# edges_v20.net
KiCad netlist of a schematic drawn in EAGLE
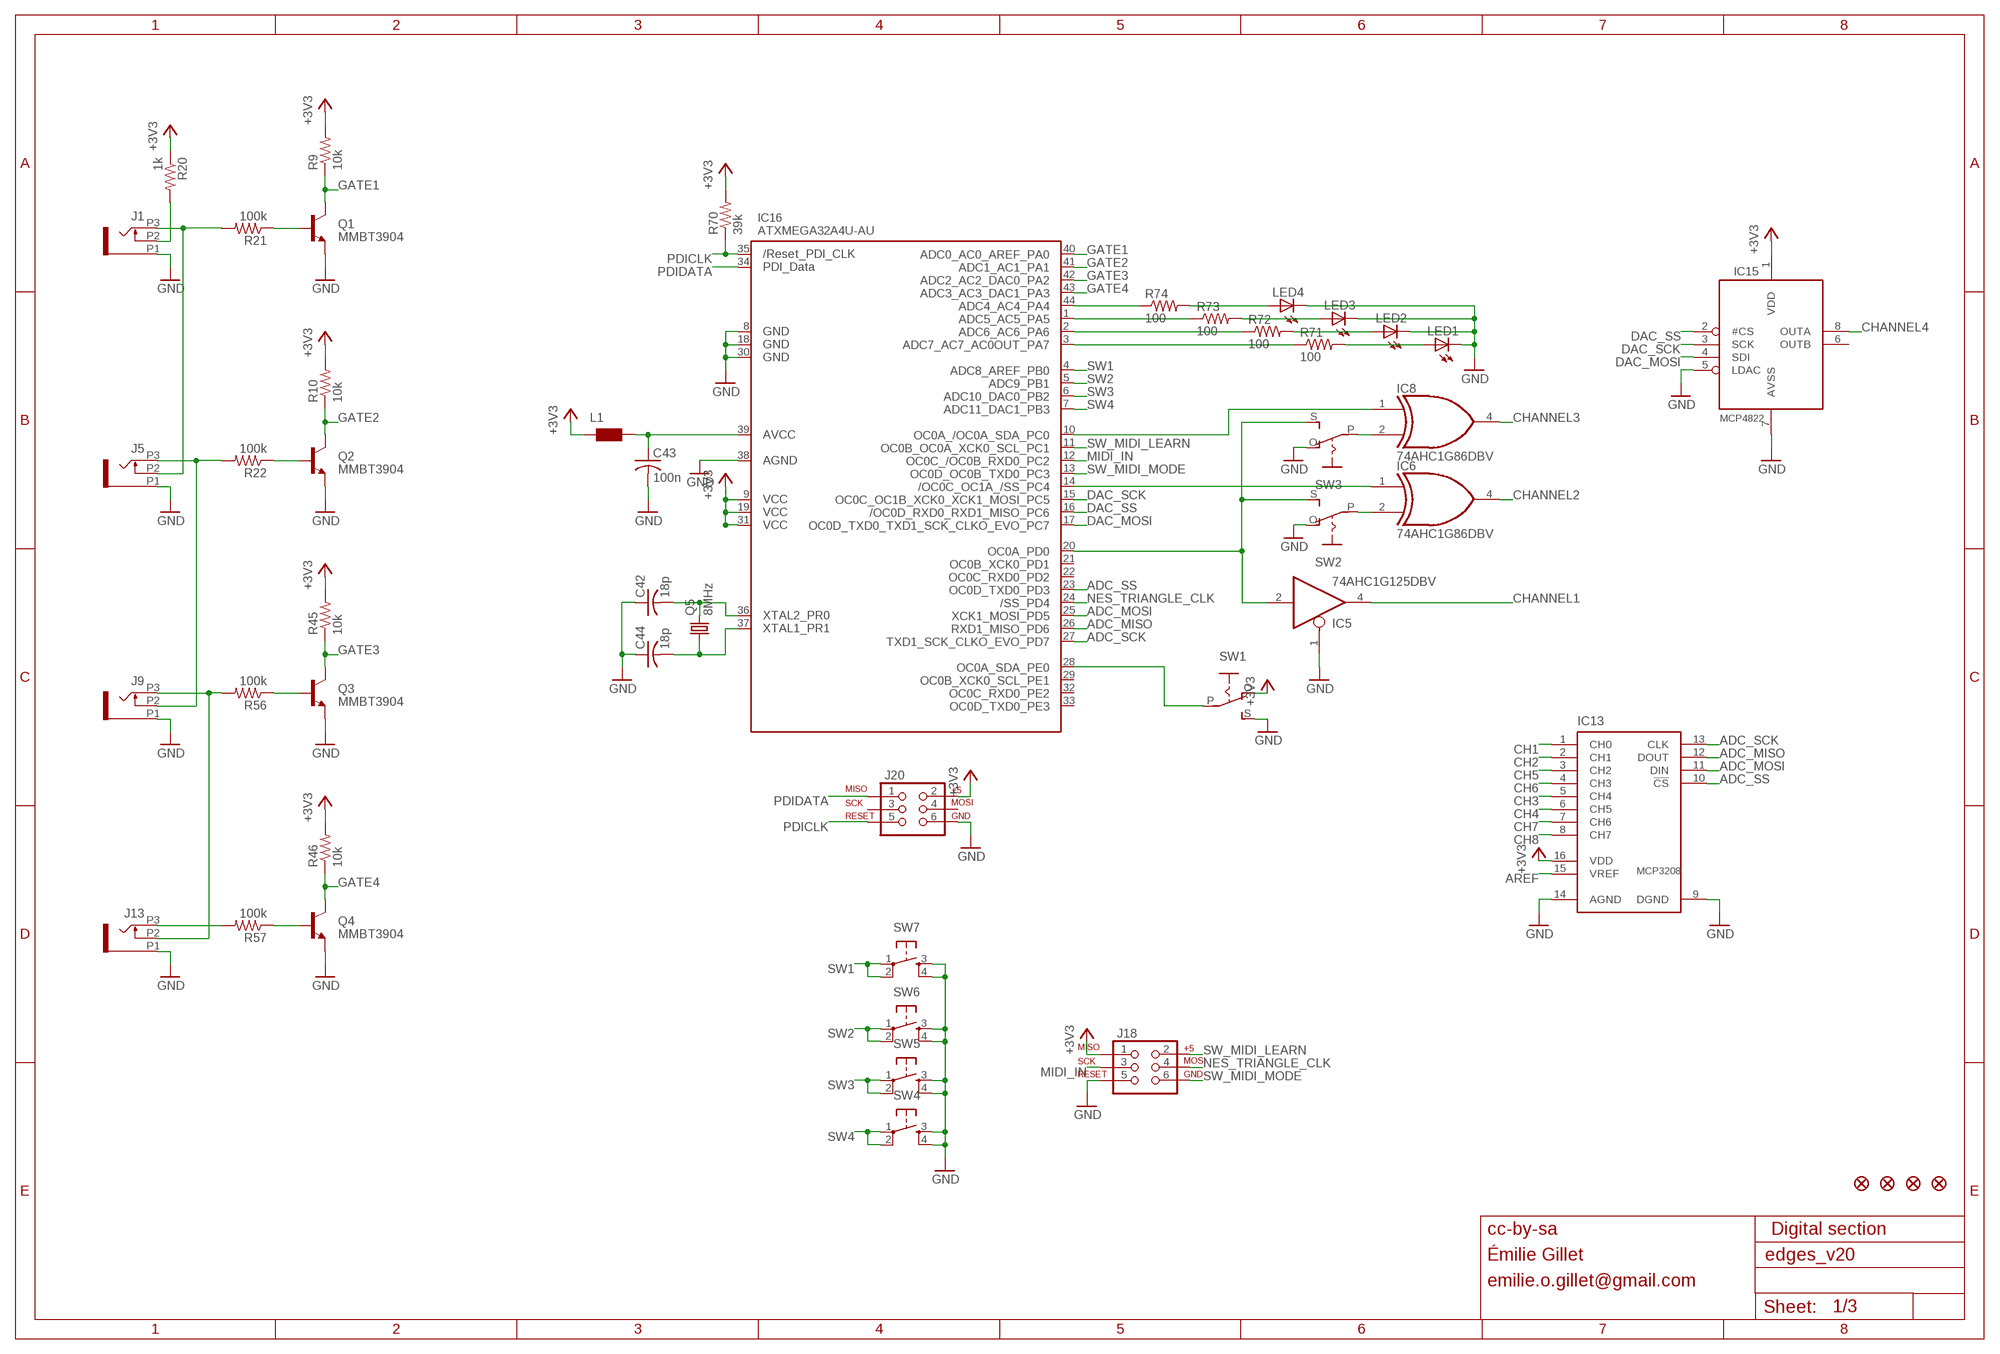
[diagram p0: schematic, sheet 1]
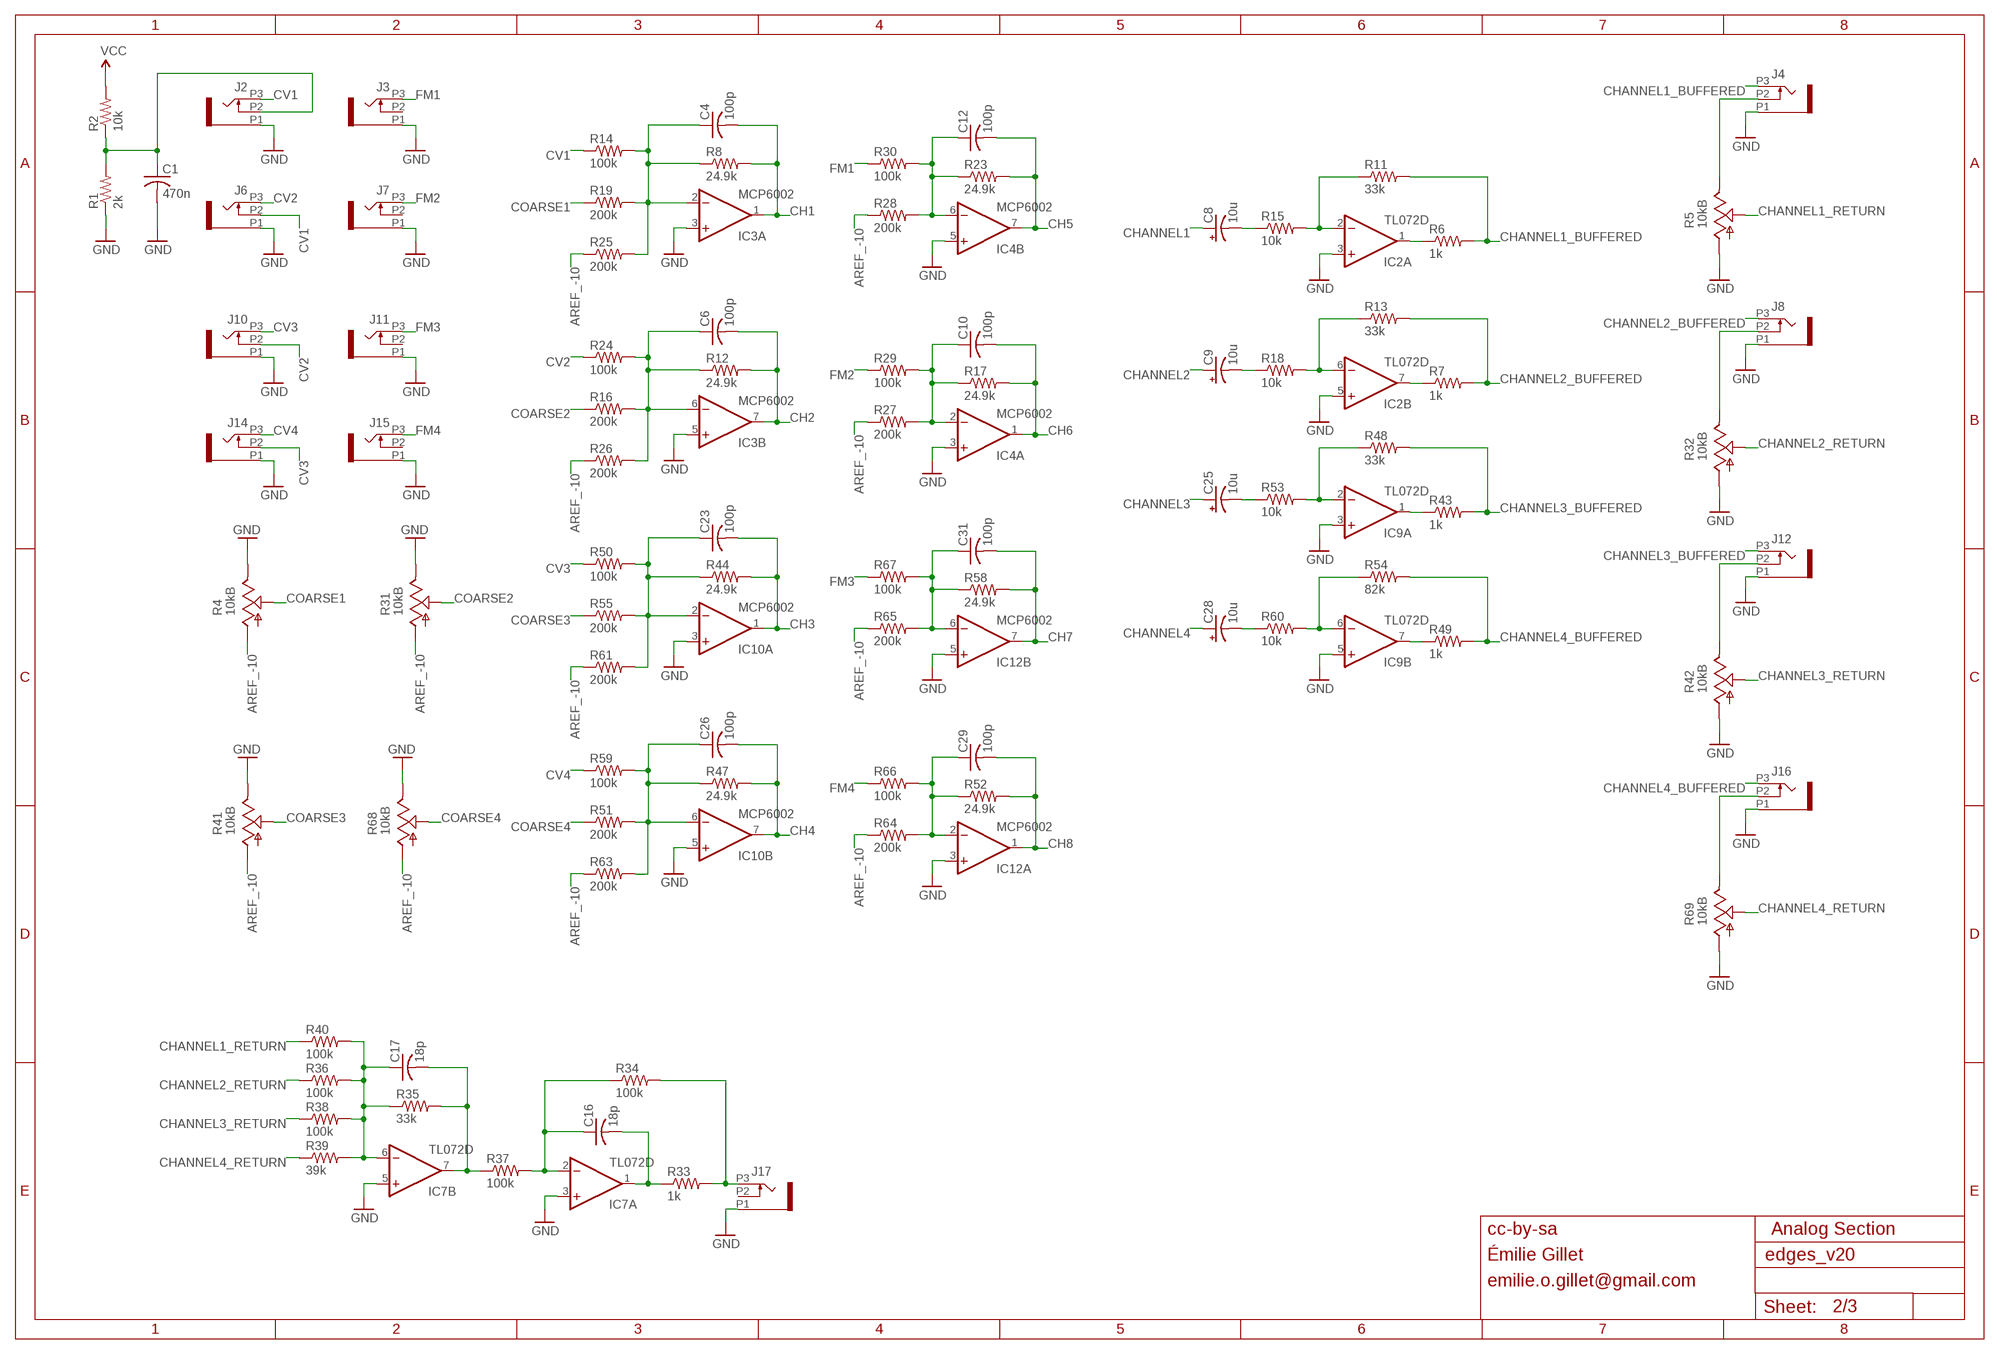
[diagram p1: schematic, sheet 2]
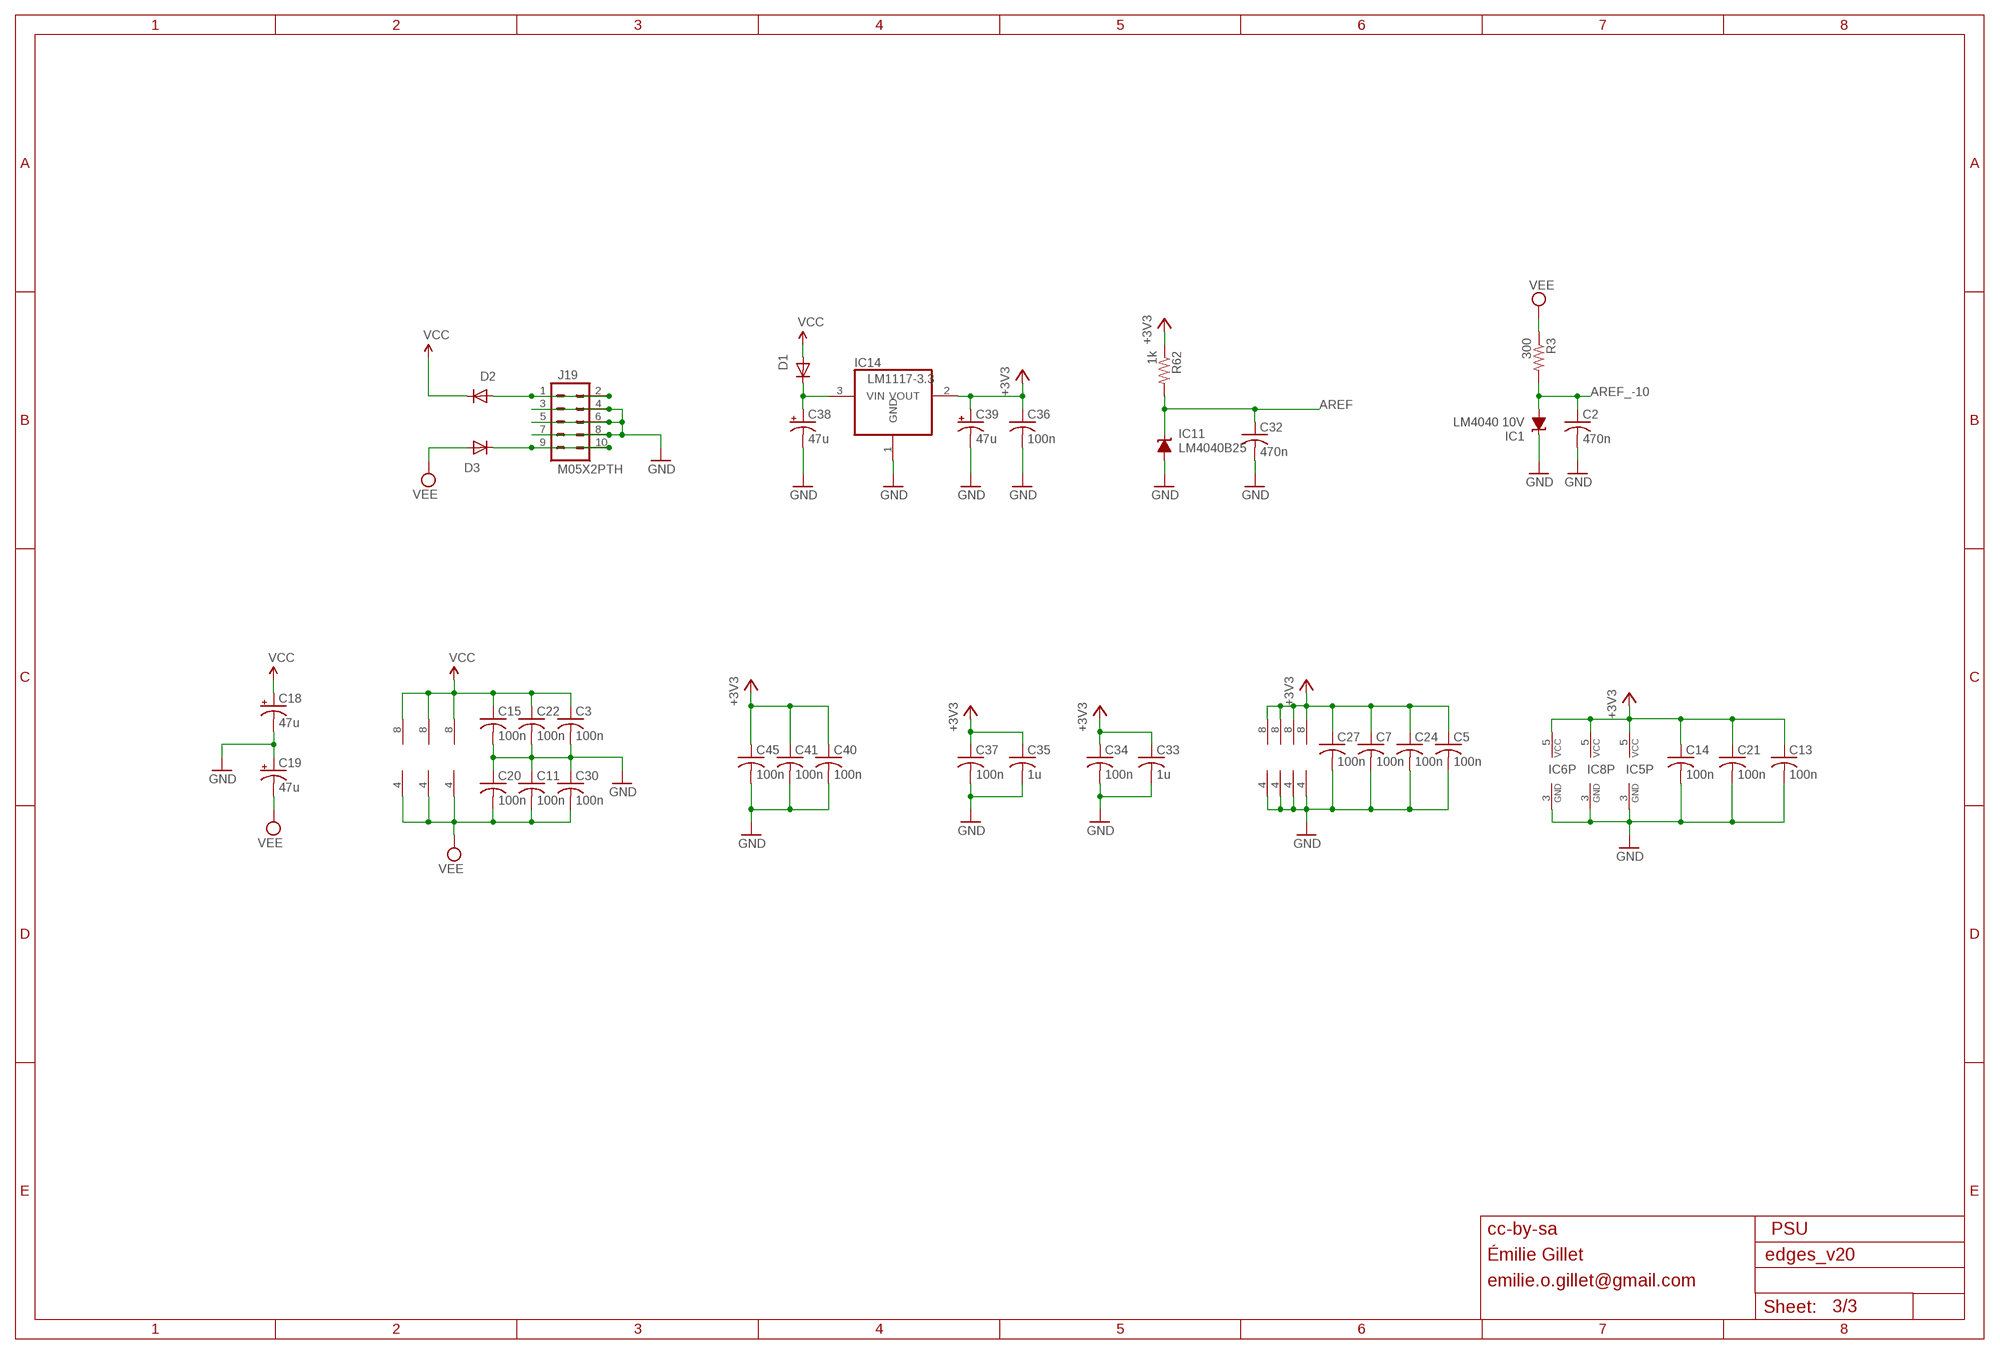
[diagram p2: schematic, sheet 3]

(export (version "E")
  (design (tool "Eeschema 10.0.6"))
  (components
    (comp (ref "C42")
      (value "18p")
      (footprint "eagle-import:C0603")
      (libsource (lib "eagle-import") (part "C-USC0603"))
    )
    (comp (ref "C43")
      (value "100n")
      (footprint "eagle-import:C0603")
      (libsource (lib "eagle-import") (part "C-USC0603"))
    )
    (comp (ref "C44")
      (value "18p")
      (footprint "eagle-import:C0603")
      (libsource (lib "eagle-import") (part "C-USC0603"))
    )
    (comp (ref "IC5")
      (value "74AHC1G125DBV")
      (footprint "eagle-import:SOT23-5")
      (libsource (lib "eagle-import") (part "741G125DBVAHC"))
    )
    (comp (ref "IC6")
      (value "74AHC1G86DBV")
      (footprint "eagle-import:SOT23-5")
      (libsource (lib "eagle-import") (part "741G86DBVAHC"))
    )
    (comp (ref "IC8")
      (value "74AHC1G86DBV")
      (footprint "eagle-import:SOT23-5")
      (libsource (lib "eagle-import") (part "741G86DBVAHC"))
    )
    (comp (ref "IC13")
      (value "MCP3208")
      (footprint "eagle-import:SO16")
      (libsource (lib "eagle-import") (part "MCP3208"))
    )
    (comp (ref "IC15")
      (value "MCP4822")
      (footprint "eagle-import:SO08")
      (libsource (lib "eagle-import") (part "MCP4822SO08"))
    )
    (comp (ref "IC16")
      (value "ATXMEGA32A4U-AU")
      (footprint "eagle-import:TQFP44")
      (libsource (lib "eagle-import") (part "AVR_XMEGA_A4_44A"))
    )
    (comp (ref "J1")
      (value "PJ301_THONKICONN6")
      (footprint "eagle-import:WQP_PJ_301M6")
      (libsource (lib "eagle-import") (part "PJ301_THONKICONN6"))
    )
    (comp (ref "J5")
      (value "PJ301_THONKICONN6")
      (footprint "eagle-import:WQP_PJ_301M6")
      (libsource (lib "eagle-import") (part "PJ301_THONKICONN6"))
    )
    (comp (ref "J9")
      (value "PJ301_THONKICONN6")
      (footprint "eagle-import:WQP_PJ_301M6")
      (libsource (lib "eagle-import") (part "PJ301_THONKICONN6"))
    )
    (comp (ref "J13")
      (value "PJ301_THONKICONN6")
      (footprint "eagle-import:WQP_PJ_301M6")
      (libsource (lib "eagle-import") (part "PJ301_THONKICONN6"))
    )
    (comp (ref "J18")
      (value "AVR_SPI_PRG_6PTH")
      (footprint "eagle-import:2X3")
      (libsource (lib "eagle-import") (part "AVR_SPI_PRG_6PTH"))
    )
    (comp (ref "J20")
      (value "AVR_SPI_PRG_6PTH")
      (footprint "eagle-import:2X3")
      (libsource (lib "eagle-import") (part "AVR_SPI_PRG_6PTH"))
    )
    (comp (ref "JP1")
      (value "FIDUCIAL1X2")
      (footprint "eagle-import:FIDUCIAL-1X2")
      (libsource (lib "eagle-import") (part "FIDUCIAL1X2"))
    )
    (comp (ref "JP2")
      (value "FIDUCIAL1X2")
      (footprint "eagle-import:FIDUCIAL-1X2")
      (libsource (lib "eagle-import") (part "FIDUCIAL1X2"))
    )
    (comp (ref "JP3")
      (value "FIDUCIAL1X2")
      (footprint "eagle-import:FIDUCIAL-1X2")
      (libsource (lib "eagle-import") (part "FIDUCIAL1X2"))
    )
    (comp (ref "JP4")
      (value "FIDUCIAL1X2")
      (footprint "eagle-import:FIDUCIAL-1X2")
      (libsource (lib "eagle-import") (part "FIDUCIAL1X2"))
    )
    (comp (ref "L1")
      (value "WE-CBF_0603")
      (footprint "eagle-import:0603")
      (libsource (lib "eagle-import") (part "WE-CBF_0603"))
    )
    (comp (ref "LED1")
      (value "LED3MM")
      (footprint "eagle-import:LED3MM")
      (libsource (lib "eagle-import") (part "LED3MM"))
    )
    (comp (ref "LED2")
      (value "LED3MM")
      (footprint "eagle-import:LED3MM")
      (libsource (lib "eagle-import") (part "LED3MM"))
    )
    (comp (ref "LED3")
      (value "LED3MM")
      (footprint "eagle-import:LED3MM")
      (libsource (lib "eagle-import") (part "LED3MM"))
    )
    (comp (ref "LED4")
      (value "LED3MM")
      (footprint "eagle-import:LED3MM")
      (libsource (lib "eagle-import") (part "LED3MM"))
    )
    (comp (ref "Q1")
      (value "MMBT3904")
      (footprint "eagle-import:SOT23-BEC")
      (libsource (lib "eagle-import") (part "-NPN-SOT23-BECMMBT3904LT1"))
    )
    (comp (ref "Q2")
      (value "MMBT3904")
      (footprint "eagle-import:SOT23-BEC")
      (libsource (lib "eagle-import") (part "-NPN-SOT23-BECMMBT3904LT1"))
    )
    (comp (ref "Q3")
      (value "MMBT3904")
      (footprint "eagle-import:SOT23-BEC")
      (libsource (lib "eagle-import") (part "-NPN-SOT23-BECMMBT3904LT1"))
    )
    (comp (ref "Q4")
      (value "MMBT3904")
      (footprint "eagle-import:SOT23-BEC")
      (libsource (lib "eagle-import") (part "-NPN-SOT23-BECMMBT3904LT1"))
    )
    (comp (ref "Q5")
      (value "8MHz")
      (footprint "eagle-import:HC49U70")
      (libsource (lib "eagle-import") (part "CRYSTALHC49U70"))
    )
    (comp (ref "R9")
      (value "10k")
      (footprint "eagle-import:R0603")
      (libsource (lib "eagle-import") (part "R-US_R0603"))
    )
    (comp (ref "R10")
      (value "10k")
      (footprint "eagle-import:R0603")
      (libsource (lib "eagle-import") (part "R-US_R0603"))
    )
    (comp (ref "R20")
      (value "1k")
      (footprint "eagle-import:R0603")
      (libsource (lib "eagle-import") (part "R-US_R0603"))
    )
    (comp (ref "R21")
      (value "100k")
      (footprint "eagle-import:R0603")
      (libsource (lib "eagle-import") (part "R-US_R0603"))
    )
    (comp (ref "R22")
      (value "100k")
      (footprint "eagle-import:R0603")
      (libsource (lib "eagle-import") (part "R-US_R0603"))
    )
    (comp (ref "R45")
      (value "10k")
      (footprint "eagle-import:R0603")
      (libsource (lib "eagle-import") (part "R-US_R0603"))
    )
    (comp (ref "R46")
      (value "10k")
      (footprint "eagle-import:R0603")
      (libsource (lib "eagle-import") (part "R-US_R0603"))
    )
    (comp (ref "R56")
      (value "100k")
      (footprint "eagle-import:R0603")
      (libsource (lib "eagle-import") (part "R-US_R0603"))
    )
    (comp (ref "R57")
      (value "100k")
      (footprint "eagle-import:R0603")
      (libsource (lib "eagle-import") (part "R-US_R0603"))
    )
    (comp (ref "R70")
      (value "39k")
      (footprint "eagle-import:R0603")
      (libsource (lib "eagle-import") (part "R-US_R0603"))
    )
    (comp (ref "R71")
      (value "100")
      (footprint "eagle-import:R0603")
      (libsource (lib "eagle-import") (part "R-US_R0603"))
    )
    (comp (ref "R72")
      (value "100")
      (footprint "eagle-import:R0603")
      (libsource (lib "eagle-import") (part "R-US_R0603"))
    )
    (comp (ref "R73")
      (value "100")
      (footprint "eagle-import:R0603")
      (libsource (lib "eagle-import") (part "R-US_R0603"))
    )
    (comp (ref "R74")
      (value "100")
      (footprint "eagle-import:R0603")
      (libsource (lib "eagle-import") (part "R-US_R0603"))
    )
    (comp (ref "SW1")
      (value "S-ON-ONSMALL_SLIDE")
      (footprint "eagle-import:ES_100SP1T6B11M2QEH_SMALL")
      (libsource (lib "eagle-import") (part "S-ON-ONSMALL_SLIDE"))
    )
    (comp (ref "SW2")
      (value "S-ON-ONSMALL_SLIDE")
      (footprint "eagle-import:ES_100SP1T6B11M2QEH_SMALL")
      (libsource (lib "eagle-import") (part "S-ON-ONSMALL_SLIDE"))
    )
    (comp (ref "SW3")
      (value "S-ON-ONSMALL_SLIDE")
      (footprint "eagle-import:ES_100SP1T6B11M2QEH_SMALL")
      (libsource (lib "eagle-import") (part "S-ON-ONSMALL_SLIDE"))
    )
    (comp (ref "SW4")
      (value "TAC_SWITCHPTH")
      (footprint "eagle-import:TACTILE-PTH")
      (libsource (lib "eagle-import") (part "TAC_SWITCHPTH"))
    )
    (comp (ref "SW5")
      (value "TAC_SWITCHPTH")
      (footprint "eagle-import:TACTILE-PTH")
      (libsource (lib "eagle-import") (part "TAC_SWITCHPTH"))
    )
    (comp (ref "SW6")
      (value "TAC_SWITCHPTH")
      (footprint "eagle-import:TACTILE-PTH")
      (libsource (lib "eagle-import") (part "TAC_SWITCHPTH"))
    )
    (comp (ref "SW7")
      (value "TAC_SWITCHPTH")
      (footprint "eagle-import:TACTILE-PTH")
      (libsource (lib "eagle-import") (part "TAC_SWITCHPTH"))
    )
    (comp (ref "C2")
      (value "470n")
      (footprint "eagle-import:C0603")
      (libsource (lib "eagle-import") (part "C-USC0603"))
    )
    (comp (ref "C3")
      (value "100n")
      (footprint "eagle-import:C0603")
      (libsource (lib "eagle-import") (part "C-USC0603"))
    )
    (comp (ref "C5")
      (value "100n")
      (footprint "eagle-import:C0603")
      (libsource (lib "eagle-import") (part "C-USC0603"))
    )
    (comp (ref "C7")
      (value "100n")
      (footprint "eagle-import:C0603")
      (libsource (lib "eagle-import") (part "C-USC0603"))
    )
    (comp (ref "C11")
      (value "100n")
      (footprint "eagle-import:C0603")
      (libsource (lib "eagle-import") (part "C-USC0603"))
    )
    (comp (ref "C13")
      (value "100n")
      (footprint "eagle-import:C0603")
      (libsource (lib "eagle-import") (part "C-USC0603"))
    )
    (comp (ref "C14")
      (value "100n")
      (footprint "eagle-import:C0603")
      (libsource (lib "eagle-import") (part "C-USC0603"))
    )
    (comp (ref "C15")
      (value "100n")
      (footprint "eagle-import:C0603")
      (libsource (lib "eagle-import") (part "C-USC0603"))
    )
    (comp (ref "C18")
      (value "47u")
      (footprint "eagle-import:PANASONIC_D")
      (libsource (lib "eagle-import") (part "CPOL-USD"))
    )
    (comp (ref "C19")
      (value "47u")
      (footprint "eagle-import:PANASONIC_D")
      (libsource (lib "eagle-import") (part "CPOL-USD"))
    )
    (comp (ref "C20")
      (value "100n")
      (footprint "eagle-import:C0603")
      (libsource (lib "eagle-import") (part "C-USC0603"))
    )
    (comp (ref "C21")
      (value "100n")
      (footprint "eagle-import:C0603")
      (libsource (lib "eagle-import") (part "C-USC0603"))
    )
    (comp (ref "C22")
      (value "100n")
      (footprint "eagle-import:C0603")
      (libsource (lib "eagle-import") (part "C-USC0603"))
    )
    (comp (ref "C24")
      (value "100n")
      (footprint "eagle-import:C0603")
      (libsource (lib "eagle-import") (part "C-USC0603"))
    )
    (comp (ref "C27")
      (value "100n")
      (footprint "eagle-import:C0603")
      (libsource (lib "eagle-import") (part "C-USC0603"))
    )
    (comp (ref "C30")
      (value "100n")
      (footprint "eagle-import:C0603")
      (libsource (lib "eagle-import") (part "C-USC0603"))
    )
    (comp (ref "C32")
      (value "470n")
      (footprint "eagle-import:C0603")
      (libsource (lib "eagle-import") (part "C-USC0603"))
    )
    (comp (ref "C33")
      (value "1u")
      (footprint "eagle-import:C0603")
      (libsource (lib "eagle-import") (part "C-USC0603"))
    )
    (comp (ref "C34")
      (value "100n")
      (footprint "eagle-import:C0603")
      (libsource (lib "eagle-import") (part "C-USC0603"))
    )
    (comp (ref "C35")
      (value "1u")
      (footprint "eagle-import:C0603")
      (libsource (lib "eagle-import") (part "C-USC0603"))
    )
    (comp (ref "C36")
      (value "100n")
      (footprint "eagle-import:C0603")
      (libsource (lib "eagle-import") (part "C-USC0603"))
    )
    (comp (ref "C37")
      (value "100n")
      (footprint "eagle-import:C0603")
      (libsource (lib "eagle-import") (part "C-USC0603"))
    )
    (comp (ref "C38")
      (value "47u")
      (footprint "eagle-import:PANASONIC_D")
      (libsource (lib "eagle-import") (part "CPOL-USD"))
    )
    (comp (ref "C39")
      (value "47u")
      (footprint "eagle-import:PANASONIC_D")
      (libsource (lib "eagle-import") (part "CPOL-USD"))
    )
    (comp (ref "C40")
      (value "100n")
      (footprint "eagle-import:C0603")
      (libsource (lib "eagle-import") (part "C-USC0603"))
    )
    (comp (ref "C41")
      (value "100n")
      (footprint "eagle-import:C0603")
      (libsource (lib "eagle-import") (part "C-USC0603"))
    )
    (comp (ref "C45")
      (value "100n")
      (footprint "eagle-import:C0603")
      (libsource (lib "eagle-import") (part "C-USC0603"))
    )
    (comp (ref "D1")
      (value "1N5819HW")
      (footprint "eagle-import:SOD123")
      (libsource (lib "eagle-import") (part "DIODE-SOD123"))
    )
    (comp (ref "D2")
      (value "1N5819HW")
      (footprint "eagle-import:SOD123")
      (libsource (lib "eagle-import") (part "DIODE-SOD123"))
    )
    (comp (ref "D3")
      (value "1N5819HW")
      (footprint "eagle-import:SOD123")
      (libsource (lib "eagle-import") (part "DIODE-SOD123"))
    )
    (comp (ref "IC1")
      (value "LM4040 10V")
      (footprint "eagle-import:DBZ_R-PDSO-G3")
      (libsource (lib "eagle-import") (part "LM4041DBZC12"))
    )
    (comp (ref "IC2")
      (value "TL072D")
      (footprint "eagle-import:SO08")
      (libsource (lib "eagle-import") (part "TL072D"))
    )
    (comp (ref "IC3")
      (value "MCP6002")
      (footprint "eagle-import:SO08")
      (libsource (lib "eagle-import") (part "TL072D"))
    )
    (comp (ref "IC4")
      (value "MCP6002")
      (footprint "eagle-import:SO08")
      (libsource (lib "eagle-import") (part "TL072D"))
    )
    (comp (ref "IC7")
      (value "TL072D")
      (footprint "eagle-import:SO08")
      (libsource (lib "eagle-import") (part "TL072D"))
    )
    (comp (ref "IC9")
      (value "TL072D")
      (footprint "eagle-import:SO08")
      (libsource (lib "eagle-import") (part "TL072D"))
    )
    (comp (ref "IC10")
      (value "MCP6002")
      (footprint "eagle-import:SO08")
      (libsource (lib "eagle-import") (part "TL072D"))
    )
    (comp (ref "IC11")
      (value "LM4040B25")
      (footprint "eagle-import:DBZ_R-PDSO-G3")
      (libsource (lib "eagle-import") (part "LM4041DBZB12"))
    )
    (comp (ref "IC12")
      (value "MCP6002")
      (footprint "eagle-import:SO08")
      (libsource (lib "eagle-import") (part "TL072D"))
    )
    (comp (ref "IC14")
      (value "LM1117-3.3")
      (footprint "eagle-import:SOT223")
      (libsource (lib "eagle-import") (part "REG1117"))
    )
    (comp (ref "J19")
      (value "M05X2PTH")
      (footprint "eagle-import:AVR_ICSP")
      (libsource (lib "eagle-import") (part "M05X2PTH"))
    )
    (comp (ref "R3")
      (value "300")
      (footprint "eagle-import:R0603")
      (libsource (lib "eagle-import") (part "resistor_R-US_R0603"))
    )
    (comp (ref "R62")
      (value "1k")
      (footprint "eagle-import:R0603")
      (libsource (lib "eagle-import") (part "R-US_R0603"))
    )
    (comp (ref "C1")
      (value "470n")
      (footprint "eagle-import:C0603")
      (libsource (lib "eagle-import") (part "C-USC0603"))
    )
    (comp (ref "C4")
      (value "100p")
      (footprint "eagle-import:C0603")
      (libsource (lib "eagle-import") (part "C-USC0603"))
    )
    (comp (ref "C6")
      (value "100p")
      (footprint "eagle-import:C0603")
      (libsource (lib "eagle-import") (part "C-USC0603"))
    )
    (comp (ref "C8")
      (value "10u")
      (footprint "eagle-import:PANASONIC_B")
      (libsource (lib "eagle-import") (part "CPOL-USB"))
    )
    (comp (ref "C9")
      (value "10u")
      (footprint "eagle-import:PANASONIC_B")
      (libsource (lib "eagle-import") (part "CPOL-USB"))
    )
    (comp (ref "C10")
      (value "100p")
      (footprint "eagle-import:C0603")
      (libsource (lib "eagle-import") (part "C-USC0603"))
    )
    (comp (ref "C12")
      (value "100p")
      (footprint "eagle-import:C0603")
      (libsource (lib "eagle-import") (part "C-USC0603"))
    )
    (comp (ref "C16")
      (value "18p")
      (footprint "eagle-import:C0603")
      (libsource (lib "eagle-import") (part "C-USC0603"))
    )
    (comp (ref "C17")
      (value "18p")
      (footprint "eagle-import:C0603")
      (libsource (lib "eagle-import") (part "C-USC0603"))
    )
    (comp (ref "C23")
      (value "100p")
      (footprint "eagle-import:C0603")
      (libsource (lib "eagle-import") (part "C-USC0603"))
    )
    (comp (ref "C25")
      (value "10u")
      (footprint "eagle-import:PANASONIC_B")
      (libsource (lib "eagle-import") (part "CPOL-USB"))
    )
    (comp (ref "C26")
      (value "100p")
      (footprint "eagle-import:C0603")
      (libsource (lib "eagle-import") (part "C-USC0603"))
    )
    (comp (ref "C28")
      (value "10u")
      (footprint "eagle-import:PANASONIC_B")
      (libsource (lib "eagle-import") (part "CPOL-USB"))
    )
    (comp (ref "C29")
      (value "100p")
      (footprint "eagle-import:C0603")
      (libsource (lib "eagle-import") (part "C-USC0603"))
    )
    (comp (ref "C31")
      (value "100p")
      (footprint "eagle-import:C0603")
      (libsource (lib "eagle-import") (part "C-USC0603"))
    )
    (comp (ref "J2")
      (value "PJ301_THONKICONN6")
      (footprint "eagle-import:WQP_PJ_301M6")
      (libsource (lib "eagle-import") (part "PJ301_THONKICONN6"))
    )
    (comp (ref "J3")
      (value "PJ301_THONKICONN6")
      (footprint "eagle-import:WQP_PJ_301M6")
      (libsource (lib "eagle-import") (part "PJ301_THONKICONN6"))
    )
    (comp (ref "J4")
      (value "PJ301_THONKICONN6")
      (footprint "eagle-import:WQP_PJ_301M6")
      (libsource (lib "eagle-import") (part "PJ301_THONKICONN6"))
    )
    (comp (ref "J6")
      (value "PJ301_THONKICONN6")
      (footprint "eagle-import:WQP_PJ_301M6")
      (libsource (lib "eagle-import") (part "PJ301_THONKICONN6"))
    )
    (comp (ref "J7")
      (value "PJ301_THONKICONN6")
      (footprint "eagle-import:WQP_PJ_301M6")
      (libsource (lib "eagle-import") (part "PJ301_THONKICONN6"))
    )
    (comp (ref "J8")
      (value "PJ301_THONKICONN6")
      (footprint "eagle-import:WQP_PJ_301M6")
      (libsource (lib "eagle-import") (part "PJ301_THONKICONN6"))
    )
    (comp (ref "J10")
      (value "PJ301_THONKICONN6")
      (footprint "eagle-import:WQP_PJ_301M6")
      (libsource (lib "eagle-import") (part "PJ301_THONKICONN6"))
    )
    (comp (ref "J11")
      (value "PJ301_THONKICONN6")
      (footprint "eagle-import:WQP_PJ_301M6")
      (libsource (lib "eagle-import") (part "PJ301_THONKICONN6"))
    )
    (comp (ref "J12")
      (value "PJ301_THONKICONN6")
      (footprint "eagle-import:WQP_PJ_301M6")
      (libsource (lib "eagle-import") (part "PJ301_THONKICONN6"))
    )
    (comp (ref "J14")
      (value "PJ301_THONKICONN6")
      (footprint "eagle-import:WQP_PJ_301M6")
      (libsource (lib "eagle-import") (part "PJ301_THONKICONN6"))
    )
    (comp (ref "J15")
      (value "PJ301_THONKICONN6")
      (footprint "eagle-import:WQP_PJ_301M6")
      (libsource (lib "eagle-import") (part "PJ301_THONKICONN6"))
    )
    (comp (ref "J16")
      (value "PJ301_THONKICONN6")
      (footprint "eagle-import:WQP_PJ_301M6")
      (libsource (lib "eagle-import") (part "PJ301_THONKICONN6"))
    )
    (comp (ref "J17")
      (value "PJ301_THONKICONN6")
      (footprint "eagle-import:WQP_PJ_301M6")
      (libsource (lib "eagle-import") (part "PJ301_THONKICONN6"))
    )
    (comp (ref "R1")
      (value "2k")
      (footprint "eagle-import:R0603")
      (libsource (lib "eagle-import") (part "R-US_R0603"))
    )
    (comp (ref "R2")
      (value "10k")
      (footprint "eagle-import:R0603")
      (libsource (lib "eagle-import") (part "R-US_R0603"))
    )
    (comp (ref "R4")
      (value "10kB")
      (footprint "eagle-import:ALPS_POT_VERTICAL_PS")
      (libsource (lib "eagle-import") (part "POT_USVERTICAL_PS"))
    )
    (comp (ref "R5")
      (value "10kB")
      (footprint "eagle-import:ALPS_POT_VERTICAL_PS")
      (libsource (lib "eagle-import") (part "POT_USVERTICAL_PS"))
    )
    (comp (ref "R6")
      (value "1k")
      (footprint "eagle-import:R0603")
      (libsource (lib "eagle-import") (part "R-US_R0603"))
    )
    (comp (ref "R7")
      (value "1k")
      (footprint "eagle-import:R0603")
      (libsource (lib "eagle-import") (part "R-US_R0603"))
    )
    (comp (ref "R8")
      (value "24.9k")
      (footprint "eagle-import:R0603")
      (libsource (lib "eagle-import") (part "R-US_R0603"))
    )
    (comp (ref "R11")
      (value "33k")
      (footprint "eagle-import:R0603")
      (libsource (lib "eagle-import") (part "R-US_R0603"))
    )
    (comp (ref "R12")
      (value "24.9k")
      (footprint "eagle-import:R0603")
      (libsource (lib "eagle-import") (part "R-US_R0603"))
    )
    (comp (ref "R13")
      (value "33k")
      (footprint "eagle-import:R0603")
      (libsource (lib "eagle-import") (part "R-US_R0603"))
    )
    (comp (ref "R14")
      (value "100k")
      (footprint "eagle-import:R0603")
      (libsource (lib "eagle-import") (part "R-US_R0603"))
    )
    (comp (ref "R15")
      (value "10k")
      (footprint "eagle-import:R0603")
      (libsource (lib "eagle-import") (part "R-US_R0603"))
    )
    (comp (ref "R16")
      (value "200k")
      (footprint "eagle-import:R0603")
      (libsource (lib "eagle-import") (part "R-US_R0603"))
    )
    (comp (ref "R17")
      (value "24.9k")
      (footprint "eagle-import:R0603")
      (libsource (lib "eagle-import") (part "R-US_R0603"))
    )
    (comp (ref "R18")
      (value "10k")
      (footprint "eagle-import:R0603")
      (libsource (lib "eagle-import") (part "R-US_R0603"))
    )
    (comp (ref "R19")
      (value "200k")
      (footprint "eagle-import:R0603")
      (libsource (lib "eagle-import") (part "R-US_R0603"))
    )
    (comp (ref "R23")
      (value "24.9k")
      (footprint "eagle-import:R0603")
      (libsource (lib "eagle-import") (part "R-US_R0603"))
    )
    (comp (ref "R24")
      (value "100k")
      (footprint "eagle-import:R0603")
      (libsource (lib "eagle-import") (part "R-US_R0603"))
    )
    (comp (ref "R25")
      (value "200k")
      (footprint "eagle-import:R0603")
      (libsource (lib "eagle-import") (part "R-US_R0603"))
    )
    (comp (ref "R26")
      (value "200k")
      (footprint "eagle-import:R0603")
      (libsource (lib "eagle-import") (part "R-US_R0603"))
    )
    (comp (ref "R27")
      (value "200k")
      (footprint "eagle-import:R0603")
      (libsource (lib "eagle-import") (part "R-US_R0603"))
    )
    (comp (ref "R28")
      (value "200k")
      (footprint "eagle-import:R0603")
      (libsource (lib "eagle-import") (part "R-US_R0603"))
    )
    (comp (ref "R29")
      (value "100k")
      (footprint "eagle-import:R0603")
      (libsource (lib "eagle-import") (part "R-US_R0603"))
    )
    (comp (ref "R30")
      (value "100k")
      (footprint "eagle-import:R0603")
      (libsource (lib "eagle-import") (part "R-US_R0603"))
    )
    (comp (ref "R31")
      (value "10kB")
      (footprint "eagle-import:ALPS_POT_VERTICAL_PS")
      (libsource (lib "eagle-import") (part "POT_USVERTICAL_PS"))
    )
    (comp (ref "R32")
      (value "10kB")
      (footprint "eagle-import:ALPS_POT_VERTICAL_PS")
      (libsource (lib "eagle-import") (part "POT_USVERTICAL_PS"))
    )
    (comp (ref "R33")
      (value "1k")
      (footprint "eagle-import:R0603")
      (libsource (lib "eagle-import") (part "R-US_R0603"))
    )
    (comp (ref "R34")
      (value "100k")
      (footprint "eagle-import:R0603")
      (libsource (lib "eagle-import") (part "R-US_R0603"))
    )
    (comp (ref "R35")
      (value "33k")
      (footprint "eagle-import:R0603")
      (libsource (lib "eagle-import") (part "R-US_R0603"))
    )
    (comp (ref "R36")
      (value "100k")
      (footprint "eagle-import:R0603")
      (libsource (lib "eagle-import") (part "R-US_R0603"))
    )
    (comp (ref "R37")
      (value "100k")
      (footprint "eagle-import:R0603")
      (libsource (lib "eagle-import") (part "R-US_R0603"))
    )
    (comp (ref "R38")
      (value "100k")
      (footprint "eagle-import:R0603")
      (libsource (lib "eagle-import") (part "R-US_R0603"))
    )
    (comp (ref "R39")
      (value "39k")
      (footprint "eagle-import:R0603")
      (libsource (lib "eagle-import") (part "R-US_R0603"))
    )
    (comp (ref "R40")
      (value "100k")
      (footprint "eagle-import:R0603")
      (libsource (lib "eagle-import") (part "R-US_R0603"))
    )
    (comp (ref "R41")
      (value "10kB")
      (footprint "eagle-import:ALPS_POT_VERTICAL_PS")
      (libsource (lib "eagle-import") (part "POT_USVERTICAL_PS"))
    )
    (comp (ref "R42")
      (value "10kB")
      (footprint "eagle-import:ALPS_POT_VERTICAL_PS")
      (libsource (lib "eagle-import") (part "POT_USVERTICAL_PS"))
    )
    (comp (ref "R43")
      (value "1k")
      (footprint "eagle-import:R0603")
      (libsource (lib "eagle-import") (part "R-US_R0603"))
    )
    (comp (ref "R44")
      (value "24.9k")
      (footprint "eagle-import:R0603")
      (libsource (lib "eagle-import") (part "R-US_R0603"))
    )
    (comp (ref "R47")
      (value "24.9k")
      (footprint "eagle-import:R0603")
      (libsource (lib "eagle-import") (part "R-US_R0603"))
    )
    (comp (ref "R48")
      (value "33k")
      (footprint "eagle-import:R0603")
      (libsource (lib "eagle-import") (part "R-US_R0603"))
    )
    (comp (ref "R49")
      (value "1k")
      (footprint "eagle-import:R0603")
      (libsource (lib "eagle-import") (part "R-US_R0603"))
    )
    (comp (ref "R50")
      (value "100k")
      (footprint "eagle-import:R0603")
      (libsource (lib "eagle-import") (part "R-US_R0603"))
    )
    (comp (ref "R51")
      (value "200k")
      (footprint "eagle-import:R0603")
      (libsource (lib "eagle-import") (part "R-US_R0603"))
    )
    (comp (ref "R52")
      (value "24.9k")
      (footprint "eagle-import:R0603")
      (libsource (lib "eagle-import") (part "R-US_R0603"))
    )
    (comp (ref "R53")
      (value "10k")
      (footprint "eagle-import:R0603")
      (libsource (lib "eagle-import") (part "R-US_R0603"))
    )
    (comp (ref "R54")
      (value "82k")
      (footprint "eagle-import:R0603")
      (libsource (lib "eagle-import") (part "R-US_R0603"))
    )
    (comp (ref "R55")
      (value "200k")
      (footprint "eagle-import:R0603")
      (libsource (lib "eagle-import") (part "R-US_R0603"))
    )
    (comp (ref "R58")
      (value "24.9k")
      (footprint "eagle-import:R0603")
      (libsource (lib "eagle-import") (part "R-US_R0603"))
    )
    (comp (ref "R59")
      (value "100k")
      (footprint "eagle-import:R0603")
      (libsource (lib "eagle-import") (part "R-US_R0603"))
    )
    (comp (ref "R60")
      (value "10k")
      (footprint "eagle-import:R0603")
      (libsource (lib "eagle-import") (part "R-US_R0603"))
    )
    (comp (ref "R61")
      (value "200k")
      (footprint "eagle-import:R0603")
      (libsource (lib "eagle-import") (part "R-US_R0603"))
    )
    (comp (ref "R63")
      (value "200k")
      (footprint "eagle-import:R0603")
      (libsource (lib "eagle-import") (part "R-US_R0603"))
    )
    (comp (ref "R64")
      (value "200k")
      (footprint "eagle-import:R0603")
      (libsource (lib "eagle-import") (part "R-US_R0603"))
    )
    (comp (ref "R65")
      (value "200k")
      (footprint "eagle-import:R0603")
      (libsource (lib "eagle-import") (part "R-US_R0603"))
    )
    (comp (ref "R66")
      (value "100k")
      (footprint "eagle-import:R0603")
      (libsource (lib "eagle-import") (part "R-US_R0603"))
    )
    (comp (ref "R67")
      (value "100k")
      (footprint "eagle-import:R0603")
      (libsource (lib "eagle-import") (part "R-US_R0603"))
    )
    (comp (ref "R68")
      (value "10kB")
      (footprint "eagle-import:ALPS_POT_VERTICAL_PS")
      (libsource (lib "eagle-import") (part "POT_USVERTICAL_PS"))
    )
    (comp (ref "R69")
      (value "10kB")
      (footprint "eagle-import:ALPS_POT_VERTICAL_PS")
      (libsource (lib "eagle-import") (part "POT_USVERTICAL_PS"))
    )
  )
  (nets
    (net (code "1") (name "+3V3") (class "Default")
      (node (ref "C13") (pin "1") (pinfunction "1_1") (pintype "passive"))
      (node (ref "C14") (pin "1") (pinfunction "1_1") (pintype "passive"))
      (node (ref "C21") (pin "1") (pinfunction "1_1") (pintype "passive"))
      (node (ref "C24") (pin "1") (pinfunction "1_1") (pintype "passive"))
      (node (ref "C27") (pin "1") (pinfunction "1_1") (pintype "passive"))
      (node (ref "C33") (pin "1") (pinfunction "1_1") (pintype "passive"))
      (node (ref "C34") (pin "1") (pinfunction "1_1") (pintype "passive"))
      (node (ref "C35") (pin "1") (pinfunction "1_1") (pintype "passive"))
      (node (ref "C36") (pin "1") (pinfunction "1_1") (pintype "passive"))
      (node (ref "C37") (pin "1") (pinfunction "1_1") (pintype "passive"))
      (node (ref "C39") (pin "+") (pinfunction "+_+") (pintype "passive"))
      (node (ref "C40") (pin "1") (pinfunction "1_1") (pintype "passive"))
      (node (ref "C41") (pin "1") (pinfunction "1_1") (pintype "passive"))
      (node (ref "C45") (pin "1") (pinfunction "1_1") (pintype "passive"))
      (node (ref "C5") (pin "1") (pinfunction "1_1") (pintype "passive"))
      (node (ref "C7") (pin "1") (pinfunction "1_1") (pintype "passive"))
      (node (ref "IC10") (pin "8") (pinfunction "V+_8") (pintype "power_in"))
      (node (ref "IC12") (pin "8") (pinfunction "V+_8") (pintype "power_in"))
      (node (ref "IC13") (pin "16") (pinfunction "VDD_16") (pintype "bidirectional"))
      (node (ref "IC14") (pin "2") (pinfunction "VOUT_2") (pintype "output"))
      (node (ref "IC15") (pin "1") (pinfunction "VDD_1") (pintype "power_in"))
      (node (ref "IC16") (pin "19") (pinfunction "VCC2_19") (pintype "bidirectional"))
      (node (ref "IC16") (pin "31") (pinfunction "VCC3_31") (pintype "bidirectional"))
      (node (ref "IC16") (pin "9") (pinfunction "VCC1_9") (pintype "bidirectional"))
      (node (ref "IC3") (pin "8") (pinfunction "V+_8") (pintype "power_in"))
      (node (ref "IC4") (pin "8") (pinfunction "V+_8") (pintype "power_in"))
      (node (ref "IC5") (pin "5") (pinfunction "VCC_5") (pintype "power_in"))
      (node (ref "IC6") (pin "5") (pinfunction "VCC_5") (pintype "power_in"))
      (node (ref "IC8") (pin "5") (pinfunction "VCC_5") (pintype "power_in"))
      (node (ref "J18") (pin "1") (pinfunction "1_1") (pintype "passive"))
      (node (ref "J20") (pin "2") (pinfunction "2_2") (pintype "passive"))
      (node (ref "L1") (pin "1") (pinfunction "1_1") (pintype "passive"))
      (node (ref "R10") (pin "2") (pinfunction "2_2") (pintype "passive"))
      (node (ref "R20") (pin "1") (pinfunction "1_1") (pintype "passive"))
      (node (ref "R45") (pin "2") (pinfunction "2_2") (pintype "passive"))
      (node (ref "R46") (pin "2") (pinfunction "2_2") (pintype "passive"))
      (node (ref "R62") (pin "1") (pinfunction "1_1") (pintype "passive"))
      (node (ref "R70") (pin "2") (pinfunction "2_2") (pintype "passive"))
      (node (ref "R9") (pin "2") (pinfunction "2_2") (pintype "passive"))
      (node (ref "SW1") (pin "O") (pinfunction "O_O") (pintype "passive"))
    )
    (net (code "2") (name "ADC_MISO") (class "Default")
      (node (ref "IC13") (pin "12") (pinfunction "DOUT_12") (pintype "bidirectional"))
      (node (ref "IC16") (pin "26") (pinfunction "PD6_26") (pintype "bidirectional"))
    )
    (net (code "3") (name "ADC_MOSI") (class "Default")
      (node (ref "IC13") (pin "11") (pinfunction "DIN_11") (pintype "bidirectional"))
      (node (ref "IC16") (pin "25") (pinfunction "PD5_25") (pintype "bidirectional"))
    )
    (net (code "4") (name "ADC_SCK") (class "Default")
      (node (ref "IC13") (pin "13") (pinfunction "CLK_13") (pintype "bidirectional"))
      (node (ref "IC16") (pin "27") (pinfunction "PD7_27") (pintype "bidirectional"))
    )
    (net (code "5") (name "ADC_SS") (class "Default")
      (node (ref "IC13") (pin "10") (pinfunction "~{CS}_10") (pintype "bidirectional"))
      (node (ref "IC16") (pin "23") (pinfunction "PD3_23") (pintype "bidirectional"))
    )
    (net (code "6") (name "AREF") (class "Default")
      (node (ref "C32") (pin "1") (pinfunction "1_1") (pintype "passive"))
      (node (ref "IC11") (pin "1") (pinfunction "C_1") (pintype "passive"))
      (node (ref "IC13") (pin "15") (pinfunction "VREF_15") (pintype "bidirectional"))
      (node (ref "R62") (pin "2") (pinfunction "2_2") (pintype "passive"))
    )
    (net (code "7") (name "AREF_-10") (class "Default")
      (node (ref "C2") (pin "1") (pinfunction "1_1") (pintype "passive"))
      (node (ref "IC1") (pin "2") (pinfunction "A_2") (pintype "passive"))
      (node (ref "R25") (pin "1") (pinfunction "1_1") (pintype "passive"))
      (node (ref "R26") (pin "1") (pinfunction "1_1") (pintype "passive"))
      (node (ref "R27") (pin "1") (pinfunction "1_1") (pintype "passive"))
      (node (ref "R28") (pin "1") (pinfunction "1_1") (pintype "passive"))
      (node (ref "R3") (pin "2") (pinfunction "2_2") (pintype "passive"))
      (node (ref "R31") (pin "P$3") (pinfunction "A_P$3") (pintype "passive"))
      (node (ref "R4") (pin "P$3") (pinfunction "A_P$3") (pintype "passive"))
      (node (ref "R41") (pin "P$3") (pinfunction "A_P$3") (pintype "passive"))
      (node (ref "R61") (pin "1") (pinfunction "1_1") (pintype "passive"))
      (node (ref "R63") (pin "1") (pinfunction "1_1") (pintype "passive"))
      (node (ref "R64") (pin "1") (pinfunction "1_1") (pintype "passive"))
      (node (ref "R65") (pin "1") (pinfunction "1_1") (pintype "passive"))
      (node (ref "R68") (pin "P$3") (pinfunction "A_P$3") (pintype "passive"))
    )
    (net (code "8") (name "CH1") (class "Default")
      (node (ref "C4") (pin "2") (pinfunction "2_2") (pintype "passive"))
      (node (ref "IC13") (pin "1") (pinfunction "CH0_1") (pintype "bidirectional"))
      (node (ref "IC3") (pin "1") (pinfunction "OUT_1") (pintype "output"))
      (node (ref "R8") (pin "2") (pinfunction "2_2") (pintype "passive"))
    )
    (net (code "9") (name "CH2") (class "Default")
      (node (ref "C6") (pin "2") (pinfunction "2_2") (pintype "passive"))
      (node (ref "IC13") (pin "2") (pinfunction "CH1_2") (pintype "bidirectional"))
      (node (ref "IC3") (pin "7") (pinfunction "OUT_7") (pintype "output"))
      (node (ref "R12") (pin "2") (pinfunction "2_2") (pintype "passive"))
    )
    (net (code "10") (name "CH3") (class "Default")
      (node (ref "C23") (pin "2") (pinfunction "2_2") (pintype "passive"))
      (node (ref "IC10") (pin "1") (pinfunction "OUT_1") (pintype "output"))
      (node (ref "IC13") (pin "5") (pinfunction "CH4_5") (pintype "bidirectional"))
      (node (ref "R44") (pin "2") (pinfunction "2_2") (pintype "passive"))
    )
    (net (code "11") (name "CH4") (class "Default")
      (node (ref "C26") (pin "2") (pinfunction "2_2") (pintype "passive"))
      (node (ref "IC10") (pin "7") (pinfunction "OUT_7") (pintype "output"))
      (node (ref "IC13") (pin "6") (pinfunction "CH5_6") (pintype "bidirectional"))
      (node (ref "R47") (pin "2") (pinfunction "2_2") (pintype "passive"))
    )
    (net (code "12") (name "CH5") (class "Default")
      (node (ref "C12") (pin "2") (pinfunction "2_2") (pintype "passive"))
      (node (ref "IC13") (pin "3") (pinfunction "CH2_3") (pintype "bidirectional"))
      (node (ref "IC4") (pin "7") (pinfunction "OUT_7") (pintype "output"))
      (node (ref "R23") (pin "2") (pinfunction "2_2") (pintype "passive"))
    )
    (net (code "13") (name "CH6") (class "Default")
      (node (ref "C10") (pin "2") (pinfunction "2_2") (pintype "passive"))
      (node (ref "IC13") (pin "4") (pinfunction "CH3_4") (pintype "bidirectional"))
      (node (ref "IC4") (pin "1") (pinfunction "OUT_1") (pintype "output"))
      (node (ref "R17") (pin "2") (pinfunction "2_2") (pintype "passive"))
    )
    (net (code "14") (name "CH7") (class "Default")
      (node (ref "C31") (pin "2") (pinfunction "2_2") (pintype "passive"))
      (node (ref "IC12") (pin "7") (pinfunction "OUT_7") (pintype "output"))
      (node (ref "IC13") (pin "7") (pinfunction "CH6_7") (pintype "bidirectional"))
      (node (ref "R58") (pin "2") (pinfunction "2_2") (pintype "passive"))
    )
    (net (code "15") (name "CH8") (class "Default")
      (node (ref "C29") (pin "2") (pinfunction "2_2") (pintype "passive"))
      (node (ref "IC12") (pin "1") (pinfunction "OUT_1") (pintype "output"))
      (node (ref "IC13") (pin "8") (pinfunction "CH7_8") (pintype "bidirectional"))
      (node (ref "R52") (pin "2") (pinfunction "2_2") (pintype "passive"))
    )
    (net (code "16") (name "CHANNEL1") (class "Default")
      (node (ref "C8") (pin "+") (pinfunction "+_+") (pintype "passive"))
      (node (ref "IC5") (pin "4") (pinfunction "O_4") (pintype "tri_state"))
    )
    (net (code "17") (name "CHANNEL1_BUFFERED") (class "Default")
      (node (ref "J4") (pin "P3") (pinfunction "3_P3") (pintype "passive"))
      (node (ref "R11") (pin "2") (pinfunction "2_2") (pintype "passive"))
      (node (ref "R6") (pin "2") (pinfunction "2_2") (pintype "passive"))
    )
    (net (code "18") (name "CHANNEL1_RETURN") (class "Default")
      (node (ref "R40") (pin "1") (pinfunction "1_1") (pintype "passive"))
      (node (ref "R5") (pin "P$2") (pinfunction "S_P$2") (pintype "passive"))
    )
    (net (code "19") (name "CHANNEL2") (class "Default")
      (node (ref "C9") (pin "+") (pinfunction "+_+") (pintype "passive"))
      (node (ref "IC6") (pin "4") (pinfunction "O_4") (pintype "output"))
    )
    (net (code "20") (name "CHANNEL2_BUFFERED") (class "Default")
      (node (ref "J8") (pin "P3") (pinfunction "3_P3") (pintype "passive"))
      (node (ref "R13") (pin "2") (pinfunction "2_2") (pintype "passive"))
      (node (ref "R7") (pin "2") (pinfunction "2_2") (pintype "passive"))
    )
    (net (code "21") (name "CHANNEL2_RETURN") (class "Default")
      (node (ref "R32") (pin "P$2") (pinfunction "S_P$2") (pintype "passive"))
      (node (ref "R36") (pin "1") (pinfunction "1_1") (pintype "passive"))
    )
    (net (code "22") (name "CHANNEL3") (class "Default")
      (node (ref "C25") (pin "+") (pinfunction "+_+") (pintype "passive"))
      (node (ref "IC8") (pin "4") (pinfunction "O_4") (pintype "output"))
    )
    (net (code "23") (name "CHANNEL3_BUFFERED") (class "Default")
      (node (ref "J12") (pin "P3") (pinfunction "3_P3") (pintype "passive"))
      (node (ref "R43") (pin "2") (pinfunction "2_2") (pintype "passive"))
      (node (ref "R48") (pin "2") (pinfunction "2_2") (pintype "passive"))
    )
    (net (code "24") (name "CHANNEL3_RETURN") (class "Default")
      (node (ref "R38") (pin "1") (pinfunction "1_1") (pintype "passive"))
      (node (ref "R42") (pin "P$2") (pinfunction "S_P$2") (pintype "passive"))
    )
    (net (code "25") (name "CHANNEL4") (class "Default")
      (node (ref "C28") (pin "+") (pinfunction "+_+") (pintype "passive"))
      (node (ref "IC15") (pin "8") (pinfunction "OUTA_8") (pintype "output"))
    )
    (net (code "26") (name "CHANNEL4_BUFFERED") (class "Default")
      (node (ref "J16") (pin "P3") (pinfunction "3_P3") (pintype "passive"))
      (node (ref "R49") (pin "2") (pinfunction "2_2") (pintype "passive"))
      (node (ref "R54") (pin "2") (pinfunction "2_2") (pintype "passive"))
    )
    (net (code "27") (name "CHANNEL4_RETURN") (class "Default")
      (node (ref "R39") (pin "1") (pinfunction "1_1") (pintype "passive"))
      (node (ref "R69") (pin "P$2") (pinfunction "S_P$2") (pintype "passive"))
    )
    (net (code "28") (name "COARSE1") (class "Default")
      (node (ref "R19") (pin "1") (pinfunction "1_1") (pintype "passive"))
      (node (ref "R4") (pin "P$2") (pinfunction "S_P$2") (pintype "passive"))
    )
    (net (code "29") (name "COARSE2") (class "Default")
      (node (ref "R16") (pin "1") (pinfunction "1_1") (pintype "passive"))
      (node (ref "R31") (pin "P$2") (pinfunction "S_P$2") (pintype "passive"))
    )
    (net (code "30") (name "COARSE3") (class "Default")
      (node (ref "R41") (pin "P$2") (pinfunction "S_P$2") (pintype "passive"))
      (node (ref "R55") (pin "1") (pinfunction "1_1") (pintype "passive"))
    )
    (net (code "31") (name "COARSE4") (class "Default")
      (node (ref "R51") (pin "1") (pinfunction "1_1") (pintype "passive"))
      (node (ref "R68") (pin "P$2") (pinfunction "S_P$2") (pintype "passive"))
    )
    (net (code "32") (name "CV1") (class "Default")
      (node (ref "J2") (pin "P3") (pinfunction "3_P3") (pintype "passive"))
      (node (ref "J6") (pin "P2") (pinfunction "2_P2") (pintype "passive"))
      (node (ref "R14") (pin "1") (pinfunction "1_1") (pintype "passive"))
    )
    (net (code "33") (name "CV2") (class "Default")
      (node (ref "J10") (pin "P2") (pinfunction "2_P2") (pintype "passive"))
      (node (ref "J6") (pin "P3") (pinfunction "3_P3") (pintype "passive"))
      (node (ref "R24") (pin "1") (pinfunction "1_1") (pintype "passive"))
    )
    (net (code "34") (name "CV3") (class "Default")
      (node (ref "J10") (pin "P3") (pinfunction "3_P3") (pintype "passive"))
      (node (ref "J14") (pin "P2") (pinfunction "2_P2") (pintype "passive"))
      (node (ref "R50") (pin "1") (pinfunction "1_1") (pintype "passive"))
    )
    (net (code "35") (name "CV4") (class "Default")
      (node (ref "J14") (pin "P3") (pinfunction "3_P3") (pintype "passive"))
      (node (ref "R59") (pin "1") (pinfunction "1_1") (pintype "passive"))
    )
    (net (code "36") (name "DAC_MOSI") (class "Default")
      (node (ref "IC15") (pin "4") (pinfunction "SDI_4") (pintype "input"))
      (node (ref "IC16") (pin "17") (pinfunction "PC7_17") (pintype "bidirectional"))
    )
    (net (code "37") (name "DAC_SCK") (class "Default")
      (node (ref "IC15") (pin "3") (pinfunction "SCK_3") (pintype "input"))
      (node (ref "IC16") (pin "15") (pinfunction "PC5_15") (pintype "bidirectional"))
    )
    (net (code "38") (name "DAC_SS") (class "Default")
      (node (ref "IC15") (pin "2") (pinfunction "#CS_2") (pintype "input"))
      (node (ref "IC16") (pin "16") (pinfunction "PC6_16") (pintype "bidirectional"))
    )
    (net (code "39") (name "FM1") (class "Default")
      (node (ref "J3") (pin "P3") (pinfunction "3_P3") (pintype "passive"))
      (node (ref "R30") (pin "1") (pinfunction "1_1") (pintype "passive"))
    )
    (net (code "40") (name "FM2") (class "Default")
      (node (ref "J7") (pin "P3") (pinfunction "3_P3") (pintype "passive"))
      (node (ref "R29") (pin "1") (pinfunction "1_1") (pintype "passive"))
    )
    (net (code "41") (name "FM3") (class "Default")
      (node (ref "J11") (pin "P3") (pinfunction "3_P3") (pintype "passive"))
      (node (ref "R67") (pin "1") (pinfunction "1_1") (pintype "passive"))
    )
    (net (code "42") (name "FM4") (class "Default")
      (node (ref "J15") (pin "P3") (pinfunction "3_P3") (pintype "passive"))
      (node (ref "R66") (pin "1") (pinfunction "1_1") (pintype "passive"))
    )
    (net (code "43") (name "GATE1") (class "Default")
      (node (ref "IC16") (pin "40") (pinfunction "PA0_40") (pintype "bidirectional"))
      (node (ref "Q1") (pin "C") (pinfunction "C_C") (pintype "passive"))
      (node (ref "R9") (pin "1") (pinfunction "1_1") (pintype "passive"))
    )
    (net (code "44") (name "GATE2") (class "Default")
      (node (ref "IC16") (pin "41") (pinfunction "PA1_41") (pintype "bidirectional"))
      (node (ref "Q2") (pin "C") (pinfunction "C_C") (pintype "passive"))
      (node (ref "R10") (pin "1") (pinfunction "1_1") (pintype "passive"))
    )
    (net (code "45") (name "GATE3") (class "Default")
      (node (ref "IC16") (pin "42") (pinfunction "PA2_42") (pintype "bidirectional"))
      (node (ref "Q3") (pin "C") (pinfunction "C_C") (pintype "passive"))
      (node (ref "R45") (pin "1") (pinfunction "1_1") (pintype "passive"))
    )
    (net (code "46") (name "GATE4") (class "Default")
      (node (ref "IC16") (pin "43") (pinfunction "PA3_43") (pintype "bidirectional"))
      (node (ref "Q4") (pin "C") (pinfunction "C_C") (pintype "passive"))
      (node (ref "R46") (pin "1") (pinfunction "1_1") (pintype "passive"))
    )
    (net (code "47") (name "GND") (class "Default")
      (node (ref "C1") (pin "2") (pinfunction "2_2") (pintype "passive"))
      (node (ref "C11") (pin "1") (pinfunction "1_1") (pintype "passive"))
      (node (ref "C13") (pin "2") (pinfunction "2_2") (pintype "passive"))
      (node (ref "C14") (pin "2") (pinfunction "2_2") (pintype "passive"))
      (node (ref "C15") (pin "2") (pinfunction "2_2") (pintype "passive"))
      (node (ref "C18") (pin "-") (pinfunction "-_-") (pintype "passive"))
      (node (ref "C19") (pin "+") (pinfunction "+_+") (pintype "passive"))
      (node (ref "C2") (pin "2") (pinfunction "2_2") (pintype "passive"))
      (node (ref "C20") (pin "1") (pinfunction "1_1") (pintype "passive"))
      (node (ref "C21") (pin "2") (pinfunction "2_2") (pintype "passive"))
      (node (ref "C22") (pin "2") (pinfunction "2_2") (pintype "passive"))
      (node (ref "C24") (pin "2") (pinfunction "2_2") (pintype "passive"))
      (node (ref "C27") (pin "2") (pinfunction "2_2") (pintype "passive"))
      (node (ref "C3") (pin "2") (pinfunction "2_2") (pintype "passive"))
      (node (ref "C30") (pin "1") (pinfunction "1_1") (pintype "passive"))
      (node (ref "C32") (pin "2") (pinfunction "2_2") (pintype "passive"))
      (node (ref "C33") (pin "2") (pinfunction "2_2") (pintype "passive"))
      (node (ref "C34") (pin "2") (pinfunction "2_2") (pintype "passive"))
      (node (ref "C35") (pin "2") (pinfunction "2_2") (pintype "passive"))
      (node (ref "C36") (pin "2") (pinfunction "2_2") (pintype "passive"))
      (node (ref "C37") (pin "2") (pinfunction "2_2") (pintype "passive"))
      (node (ref "C38") (pin "-") (pinfunction "-_-") (pintype "passive"))
      (node (ref "C39") (pin "-") (pinfunction "-_-") (pintype "passive"))
      (node (ref "C40") (pin "2") (pinfunction "2_2") (pintype "passive"))
      (node (ref "C41") (pin "2") (pinfunction "2_2") (pintype "passive"))
      (node (ref "C42") (pin "1") (pinfunction "1_1") (pintype "passive"))
      (node (ref "C43") (pin "2") (pinfunction "2_2") (pintype "passive"))
      (node (ref "C44") (pin "1") (pinfunction "1_1") (pintype "passive"))
      (node (ref "C45") (pin "2") (pinfunction "2_2") (pintype "passive"))
      (node (ref "C5") (pin "2") (pinfunction "2_2") (pintype "passive"))
      (node (ref "C7") (pin "2") (pinfunction "2_2") (pintype "passive"))
      (node (ref "IC1") (pin "1") (pinfunction "C_1") (pintype "passive"))
      (node (ref "IC10") (pin "3") (pinfunction "+IN_3") (pintype "input"))
      (node (ref "IC10") (pin "4") (pinfunction "V-_4") (pintype "power_in"))
      (node (ref "IC10") (pin "5") (pinfunction "+IN_5") (pintype "input"))
      (node (ref "IC11") (pin "2") (pinfunction "A_2") (pintype "passive"))
      (node (ref "IC12") (pin "3") (pinfunction "+IN_3") (pintype "input"))
      (node (ref "IC12") (pin "4") (pinfunction "V-_4") (pintype "power_in"))
      (node (ref "IC12") (pin "5") (pinfunction "+IN_5") (pintype "input"))
      (node (ref "IC13") (pin "14") (pinfunction "AGND_14") (pintype "bidirectional"))
      (node (ref "IC13") (pin "9") (pinfunction "DGND_9") (pintype "bidirectional"))
      (node (ref "IC14") (pin "1") (pinfunction "GND_1") (pintype "power_in"))
      (node (ref "IC15") (pin "5") (pinfunction "LDAC_5") (pintype "input"))
      (node (ref "IC15") (pin "7") (pinfunction "AVSS_7") (pintype "power_in"))
      (node (ref "IC16") (pin "18") (pinfunction "GND2_18") (pintype "bidirectional"))
      (node (ref "IC16") (pin "30") (pinfunction "GND3_30") (pintype "bidirectional"))
      (node (ref "IC16") (pin "38") (pinfunction "AGND_38") (pintype "bidirectional"))
      (node (ref "IC16") (pin "8") (pinfunction "GND1_8") (pintype "bidirectional"))
      (node (ref "IC2") (pin "3") (pinfunction "+IN_3") (pintype "input"))
      (node (ref "IC2") (pin "5") (pinfunction "+IN_5") (pintype "input"))
      (node (ref "IC3") (pin "3") (pinfunction "+IN_3") (pintype "input"))
      (node (ref "IC3") (pin "4") (pinfunction "V-_4") (pintype "power_in"))
      (node (ref "IC3") (pin "5") (pinfunction "+IN_5") (pintype "input"))
      (node (ref "IC4") (pin "3") (pinfunction "+IN_3") (pintype "input"))
      (node (ref "IC4") (pin "4") (pinfunction "V-_4") (pintype "power_in"))
      (node (ref "IC4") (pin "5") (pinfunction "+IN_5") (pintype "input"))
      (node (ref "IC5") (pin "1") (pinfunction "OE_1") (pintype "input"))
      (node (ref "IC5") (pin "3") (pinfunction "GND_3") (pintype "power_in"))
      (node (ref "IC6") (pin "3") (pinfunction "GND_3") (pintype "power_in"))
      (node (ref "IC7") (pin "3") (pinfunction "+IN_3") (pintype "input"))
      (node (ref "IC7") (pin "5") (pinfunction "+IN_5") (pintype "input"))
      (node (ref "IC8") (pin "3") (pinfunction "GND_3") (pintype "power_in"))
      (node (ref "IC9") (pin "3") (pinfunction "+IN_3") (pintype "input"))
      (node (ref "IC9") (pin "5") (pinfunction "+IN_5") (pintype "input"))
      (node (ref "J1") (pin "P1") (pinfunction "1_P1") (pintype "passive"))
      (node (ref "J10") (pin "P1") (pinfunction "1_P1") (pintype "passive"))
      (node (ref "J11") (pin "P1") (pinfunction "1_P1") (pintype "passive"))
      (node (ref "J12") (pin "P1") (pinfunction "1_P1") (pintype "passive"))
      (node (ref "J13") (pin "P1") (pinfunction "1_P1") (pintype "passive"))
      (node (ref "J14") (pin "P1") (pinfunction "1_P1") (pintype "passive"))
      (node (ref "J15") (pin "P1") (pinfunction "1_P1") (pintype "passive"))
      (node (ref "J16") (pin "P1") (pinfunction "1_P1") (pintype "passive"))
      (node (ref "J17") (pin "P1") (pinfunction "1_P1") (pintype "passive"))
      (node (ref "J18") (pin "5") (pinfunction "5_5") (pintype "passive"))
      (node (ref "J19") (pin "3") (pinfunction "3_3") (pintype "passive"))
      (node (ref "J19") (pin "4") (pinfunction "4_4") (pintype "passive"))
      (node (ref "J19") (pin "5") (pinfunction "5_5") (pintype "passive"))
      (node (ref "J19") (pin "6") (pinfunction "6_6") (pintype "passive"))
      (node (ref "J19") (pin "7") (pinfunction "7_7") (pintype "passive"))
      (node (ref "J19") (pin "8") (pinfunction "8_8") (pintype "passive"))
      (node (ref "J2") (pin "P1") (pinfunction "1_P1") (pintype "passive"))
      (node (ref "J20") (pin "6") (pinfunction "6_6") (pintype "passive"))
      (node (ref "J3") (pin "P1") (pinfunction "1_P1") (pintype "passive"))
      (node (ref "J4") (pin "P1") (pinfunction "1_P1") (pintype "passive"))
      (node (ref "J5") (pin "P1") (pinfunction "1_P1") (pintype "passive"))
      (node (ref "J6") (pin "P1") (pinfunction "1_P1") (pintype "passive"))
      (node (ref "J7") (pin "P1") (pinfunction "1_P1") (pintype "passive"))
      (node (ref "J8") (pin "P1") (pinfunction "1_P1") (pintype "passive"))
      (node (ref "J9") (pin "P1") (pinfunction "1_P1") (pintype "passive"))
      (node (ref "LED1") (pin "K") (pinfunction "C_K") (pintype "passive"))
      (node (ref "LED2") (pin "K") (pinfunction "C_K") (pintype "passive"))
      (node (ref "LED3") (pin "K") (pinfunction "C_K") (pintype "passive"))
      (node (ref "LED4") (pin "K") (pinfunction "C_K") (pintype "passive"))
      (node (ref "Q1") (pin "E") (pinfunction "E_E") (pintype "passive"))
      (node (ref "Q2") (pin "E") (pinfunction "E_E") (pintype "passive"))
      (node (ref "Q3") (pin "E") (pinfunction "E_E") (pintype "passive"))
      (node (ref "Q4") (pin "E") (pinfunction "E_E") (pintype "passive"))
      (node (ref "R1") (pin "1") (pinfunction "1_1") (pintype "passive"))
      (node (ref "R31") (pin "P$1") (pinfunction "E_P$1") (pintype "passive"))
      (node (ref "R32") (pin "P$3") (pinfunction "A_P$3") (pintype "passive"))
      (node (ref "R4") (pin "P$1") (pinfunction "E_P$1") (pintype "passive"))
      (node (ref "R41") (pin "P$1") (pinfunction "E_P$1") (pintype "passive"))
      (node (ref "R42") (pin "P$3") (pinfunction "A_P$3") (pintype "passive"))
      (node (ref "R5") (pin "P$3") (pinfunction "A_P$3") (pintype "passive"))
      (node (ref "R68") (pin "P$1") (pinfunction "E_P$1") (pintype "passive"))
      (node (ref "R69") (pin "P$3") (pinfunction "A_P$3") (pintype "passive"))
      (node (ref "SW1") (pin "S") (pinfunction "S_S") (pintype "passive"))
      (node (ref "SW2") (pin "O") (pinfunction "O_O") (pintype "passive"))
      (node (ref "SW3") (pin "O") (pinfunction "O_O") (pintype "passive"))
      (node (ref "SW4") (pin "3") (pinfunction "3_3") (pintype "passive"))
      (node (ref "SW4") (pin "4") (pinfunction "4_4") (pintype "passive"))
      (node (ref "SW5") (pin "3") (pinfunction "3_3") (pintype "passive"))
      (node (ref "SW5") (pin "4") (pinfunction "4_4") (pintype "passive"))
      (node (ref "SW6") (pin "3") (pinfunction "3_3") (pintype "passive"))
      (node (ref "SW6") (pin "4") (pinfunction "4_4") (pintype "passive"))
      (node (ref "SW7") (pin "3") (pinfunction "3_3") (pintype "passive"))
      (node (ref "SW7") (pin "4") (pinfunction "4_4") (pintype "passive"))
    )
    (net (code "48") (name "MIDI_IN") (class "Default")
      (node (ref "IC16") (pin "12") (pinfunction "PC2_12") (pintype "bidirectional"))
      (node (ref "J18") (pin "3") (pinfunction "3_3") (pintype "passive"))
    )
    (net (code "49") (name "NES_TRIANGLE_CLK") (class "Default")
      (node (ref "IC16") (pin "24") (pinfunction "PD4_24") (pintype "bidirectional"))
      (node (ref "J18") (pin "4") (pinfunction "4_4") (pintype "passive"))
    )
    (net (code "50") (name "Net-(C8-Pad-)") (class "Default")
      (node (ref "C8") (pin "-") (pinfunction "-_-") (pintype "passive"))
      (node (ref "R15") (pin "1") (pinfunction "1_1") (pintype "passive"))
    )
    (net (code "51") (name "Net-(C9-Pad-)") (class "Default")
      (node (ref "C9") (pin "-") (pinfunction "-_-") (pintype "passive"))
      (node (ref "R18") (pin "1") (pinfunction "1_1") (pintype "passive"))
    )
    (net (code "52") (name "Net-(C25-Pad-)") (class "Default")
      (node (ref "C25") (pin "-") (pinfunction "-_-") (pintype "passive"))
      (node (ref "R53") (pin "1") (pinfunction "1_1") (pintype "passive"))
    )
    (net (code "53") (name "Net-(C28-Pad-)") (class "Default")
      (node (ref "C28") (pin "-") (pinfunction "-_-") (pintype "passive"))
      (node (ref "R60") (pin "1") (pinfunction "1_1") (pintype "passive"))
    )
    (net (code "54") (name "Net-(D2-PadA)") (class "Default")
      (node (ref "D2") (pin "A") (pinfunction "A_A") (pintype "passive"))
      (node (ref "J19") (pin "1") (pinfunction "1_1") (pintype "passive"))
      (node (ref "J19") (pin "2") (pinfunction "2_2") (pintype "passive"))
    )
    (net (code "55") (name "Net-(D3-PadC)") (class "Default")
      (node (ref "D3") (pin "C") (pinfunction "C_C") (pintype "passive"))
      (node (ref "J19") (pin "10") (pinfunction "10_10") (pintype "passive"))
      (node (ref "J19") (pin "9") (pinfunction "9_9") (pintype "passive"))
    )
    (net (code "56") (name "Net-(IC2A--IN)") (class "Default")
      (node (ref "IC2") (pin "2") (pinfunction "-IN_2") (pintype "input"))
      (node (ref "R11") (pin "1") (pinfunction "1_1") (pintype "passive"))
      (node (ref "R15") (pin "2") (pinfunction "2_2") (pintype "passive"))
    )
    (net (code "57") (name "Net-(IC2A-OUT)") (class "Default")
      (node (ref "IC2") (pin "1") (pinfunction "OUT_1") (pintype "output"))
      (node (ref "R6") (pin "1") (pinfunction "1_1") (pintype "passive"))
    )
    (net (code "58") (name "Net-(IC2B--IN)") (class "Default")
      (node (ref "IC2") (pin "6") (pinfunction "-IN_6") (pintype "input"))
      (node (ref "R13") (pin "1") (pinfunction "1_1") (pintype "passive"))
      (node (ref "R18") (pin "2") (pinfunction "2_2") (pintype "passive"))
    )
    (net (code "59") (name "Net-(IC2B-OUT)") (class "Default")
      (node (ref "IC2") (pin "7") (pinfunction "OUT_7") (pintype "output"))
      (node (ref "R7") (pin "1") (pinfunction "1_1") (pintype "passive"))
    )
    (net (code "60") (name "Net-(IC3A--IN)") (class "Default")
      (node (ref "C4") (pin "1") (pinfunction "1_1") (pintype "passive"))
      (node (ref "IC3") (pin "2") (pinfunction "-IN_2") (pintype "input"))
      (node (ref "R14") (pin "2") (pinfunction "2_2") (pintype "passive"))
      (node (ref "R19") (pin "2") (pinfunction "2_2") (pintype "passive"))
      (node (ref "R25") (pin "2") (pinfunction "2_2") (pintype "passive"))
      (node (ref "R8") (pin "1") (pinfunction "1_1") (pintype "passive"))
    )
    (net (code "61") (name "Net-(IC3B--IN)") (class "Default")
      (node (ref "C6") (pin "1") (pinfunction "1_1") (pintype "passive"))
      (node (ref "IC3") (pin "6") (pinfunction "-IN_6") (pintype "input"))
      (node (ref "R12") (pin "1") (pinfunction "1_1") (pintype "passive"))
      (node (ref "R16") (pin "2") (pinfunction "2_2") (pintype "passive"))
      (node (ref "R24") (pin "2") (pinfunction "2_2") (pintype "passive"))
      (node (ref "R26") (pin "2") (pinfunction "2_2") (pintype "passive"))
    )
    (net (code "62") (name "Net-(IC4A--IN)") (class "Default")
      (node (ref "C10") (pin "1") (pinfunction "1_1") (pintype "passive"))
      (node (ref "IC4") (pin "2") (pinfunction "-IN_2") (pintype "input"))
      (node (ref "R17") (pin "1") (pinfunction "1_1") (pintype "passive"))
      (node (ref "R27") (pin "2") (pinfunction "2_2") (pintype "passive"))
      (node (ref "R29") (pin "2") (pinfunction "2_2") (pintype "passive"))
    )
    (net (code "63") (name "Net-(IC4B--IN)") (class "Default")
      (node (ref "C12") (pin "1") (pinfunction "1_1") (pintype "passive"))
      (node (ref "IC4") (pin "6") (pinfunction "-IN_6") (pintype "input"))
      (node (ref "R23") (pin "1") (pinfunction "1_1") (pintype "passive"))
      (node (ref "R28") (pin "2") (pinfunction "2_2") (pintype "passive"))
      (node (ref "R30") (pin "2") (pinfunction "2_2") (pintype "passive"))
    )
    (net (code "64") (name "Net-(IC6A-I1)") (class "Default")
      (node (ref "IC6") (pin "2") (pinfunction "I1_2") (pintype "input"))
      (node (ref "SW2") (pin "P") (pinfunction "P_P") (pintype "passive"))
    )
    (net (code "65") (name "Net-(IC7A--IN)") (class "Default")
      (node (ref "C16") (pin "1") (pinfunction "1_1") (pintype "passive"))
      (node (ref "IC7") (pin "2") (pinfunction "-IN_2") (pintype "input"))
      (node (ref "R34") (pin "1") (pinfunction "1_1") (pintype "passive"))
      (node (ref "R37") (pin "2") (pinfunction "2_2") (pintype "passive"))
    )
    (net (code "66") (name "Net-(IC7A-OUT)") (class "Default")
      (node (ref "C16") (pin "2") (pinfunction "2_2") (pintype "passive"))
      (node (ref "IC7") (pin "1") (pinfunction "OUT_1") (pintype "output"))
      (node (ref "R33") (pin "1") (pinfunction "1_1") (pintype "passive"))
    )
    (net (code "67") (name "Net-(IC7B--IN)") (class "Default")
      (node (ref "C17") (pin "1") (pinfunction "1_1") (pintype "passive"))
      (node (ref "IC7") (pin "6") (pinfunction "-IN_6") (pintype "input"))
      (node (ref "R35") (pin "1") (pinfunction "1_1") (pintype "passive"))
      (node (ref "R36") (pin "2") (pinfunction "2_2") (pintype "passive"))
      (node (ref "R38") (pin "2") (pinfunction "2_2") (pintype "passive"))
      (node (ref "R39") (pin "2") (pinfunction "2_2") (pintype "passive"))
      (node (ref "R40") (pin "2") (pinfunction "2_2") (pintype "passive"))
    )
    (net (code "68") (name "Net-(IC7B-OUT)") (class "Default")
      (node (ref "C17") (pin "2") (pinfunction "2_2") (pintype "passive"))
      (node (ref "IC7") (pin "7") (pinfunction "OUT_7") (pintype "output"))
      (node (ref "R35") (pin "2") (pinfunction "2_2") (pintype "passive"))
      (node (ref "R37") (pin "1") (pinfunction "1_1") (pintype "passive"))
    )
    (net (code "69") (name "Net-(IC8A-I1)") (class "Default")
      (node (ref "IC8") (pin "2") (pinfunction "I1_2") (pintype "input"))
      (node (ref "SW3") (pin "P") (pinfunction "P_P") (pintype "passive"))
    )
    (net (code "70") (name "Net-(IC9A--IN)") (class "Default")
      (node (ref "IC9") (pin "2") (pinfunction "-IN_2") (pintype "input"))
      (node (ref "R48") (pin "1") (pinfunction "1_1") (pintype "passive"))
      (node (ref "R53") (pin "2") (pinfunction "2_2") (pintype "passive"))
    )
    (net (code "71") (name "Net-(IC9A-OUT)") (class "Default")
      (node (ref "IC9") (pin "1") (pinfunction "OUT_1") (pintype "output"))
      (node (ref "R43") (pin "1") (pinfunction "1_1") (pintype "passive"))
    )
    (net (code "72") (name "Net-(IC9B--IN)") (class "Default")
      (node (ref "IC9") (pin "6") (pinfunction "-IN_6") (pintype "input"))
      (node (ref "R54") (pin "1") (pinfunction "1_1") (pintype "passive"))
      (node (ref "R60") (pin "2") (pinfunction "2_2") (pintype "passive"))
    )
    (net (code "73") (name "Net-(IC9B-OUT)") (class "Default")
      (node (ref "IC9") (pin "7") (pinfunction "OUT_7") (pintype "output"))
      (node (ref "R49") (pin "1") (pinfunction "1_1") (pintype "passive"))
    )
    (net (code "74") (name "Net-(IC10A--IN)") (class "Default")
      (node (ref "C23") (pin "1") (pinfunction "1_1") (pintype "passive"))
      (node (ref "IC10") (pin "2") (pinfunction "-IN_2") (pintype "input"))
      (node (ref "R44") (pin "1") (pinfunction "1_1") (pintype "passive"))
      (node (ref "R50") (pin "2") (pinfunction "2_2") (pintype "passive"))
      (node (ref "R55") (pin "2") (pinfunction "2_2") (pintype "passive"))
      (node (ref "R61") (pin "2") (pinfunction "2_2") (pintype "passive"))
    )
    (net (code "75") (name "Net-(IC10B--IN)") (class "Default")
      (node (ref "C26") (pin "1") (pinfunction "1_1") (pintype "passive"))
      (node (ref "IC10") (pin "6") (pinfunction "-IN_6") (pintype "input"))
      (node (ref "R47") (pin "1") (pinfunction "1_1") (pintype "passive"))
      (node (ref "R51") (pin "2") (pinfunction "2_2") (pintype "passive"))
      (node (ref "R59") (pin "2") (pinfunction "2_2") (pintype "passive"))
      (node (ref "R63") (pin "2") (pinfunction "2_2") (pintype "passive"))
    )
    (net (code "76") (name "Net-(IC12A--IN)") (class "Default")
      (node (ref "C29") (pin "1") (pinfunction "1_1") (pintype "passive"))
      (node (ref "IC12") (pin "2") (pinfunction "-IN_2") (pintype "input"))
      (node (ref "R52") (pin "1") (pinfunction "1_1") (pintype "passive"))
      (node (ref "R64") (pin "2") (pinfunction "2_2") (pintype "passive"))
      (node (ref "R66") (pin "2") (pinfunction "2_2") (pintype "passive"))
    )
    (net (code "77") (name "Net-(IC12B--IN)") (class "Default")
      (node (ref "C31") (pin "1") (pinfunction "1_1") (pintype "passive"))
      (node (ref "IC12") (pin "6") (pinfunction "-IN_6") (pintype "input"))
      (node (ref "R58") (pin "1") (pinfunction "1_1") (pintype "passive"))
      (node (ref "R65") (pin "2") (pinfunction "2_2") (pintype "passive"))
      (node (ref "R67") (pin "2") (pinfunction "2_2") (pintype "passive"))
    )
    (net (code "78") (name "Net-(IC14-VIN)") (class "Default")
      (node (ref "C38") (pin "+") (pinfunction "+_+") (pintype "passive"))
      (node (ref "D1") (pin "C") (pinfunction "C_C") (pintype "passive"))
      (node (ref "IC14") (pin "3") (pinfunction "VIN_3") (pintype "input"))
    )
    (net (code "79") (name "Net-(IC16-AVCC)") (class "Default")
      (node (ref "C43") (pin "1") (pinfunction "1_1") (pintype "passive"))
      (node (ref "IC16") (pin "39") (pinfunction "AVCC_39") (pintype "bidirectional"))
      (node (ref "L1") (pin "2") (pinfunction "2_2") (pintype "passive"))
    )
    (net (code "80") (name "Net-(IC16-PA4)") (class "Default")
      (node (ref "IC16") (pin "44") (pinfunction "PA4_44") (pintype "bidirectional"))
      (node (ref "R74") (pin "1") (pinfunction "1_1") (pintype "passive"))
    )
    (net (code "81") (name "Net-(IC16-PA5)") (class "Default")
      (node (ref "IC16") (pin "1") (pinfunction "PA5_1") (pintype "bidirectional"))
      (node (ref "R73") (pin "1") (pinfunction "1_1") (pintype "passive"))
    )
    (net (code "82") (name "Net-(IC16-PA6)") (class "Default")
      (node (ref "IC16") (pin "2") (pinfunction "PA6_2") (pintype "bidirectional"))
      (node (ref "R72") (pin "1") (pinfunction "1_1") (pintype "passive"))
    )
    (net (code "83") (name "Net-(IC16-PA7)") (class "Default")
      (node (ref "IC16") (pin "3") (pinfunction "PA7_3") (pintype "bidirectional"))
      (node (ref "R71") (pin "1") (pinfunction "1_1") (pintype "passive"))
    )
    (net (code "84") (name "Net-(IC16-PC0)") (class "Default")
      (node (ref "IC16") (pin "10") (pinfunction "PC0_10") (pintype "bidirectional"))
      (node (ref "IC8") (pin "1") (pinfunction "I0_1") (pintype "input"))
    )
    (net (code "85") (name "Net-(IC16-PC4)") (class "Default")
      (node (ref "IC16") (pin "14") (pinfunction "PC4_14") (pintype "bidirectional"))
      (node (ref "IC6") (pin "1") (pinfunction "I0_1") (pintype "input"))
    )
    (net (code "86") (name "Net-(IC16-PD0)") (class "Default")
      (node (ref "IC16") (pin "20") (pinfunction "PD0_20") (pintype "bidirectional"))
      (node (ref "IC5") (pin "2") (pinfunction "I_2") (pintype "input"))
      (node (ref "SW2") (pin "S") (pinfunction "S_S") (pintype "passive"))
      (node (ref "SW3") (pin "S") (pinfunction "S_S") (pintype "passive"))
    )
    (net (code "87") (name "Net-(IC16-PE0)") (class "Default")
      (node (ref "IC16") (pin "28") (pinfunction "PE0_28") (pintype "bidirectional"))
      (node (ref "SW1") (pin "P") (pinfunction "P_P") (pintype "passive"))
    )
    (net (code "88") (name "Net-(IC16-PR0)") (class "Default")
      (node (ref "C42") (pin "2") (pinfunction "2_2") (pintype "passive"))
      (node (ref "IC16") (pin "36") (pinfunction "PR0_36") (pintype "bidirectional"))
      (node (ref "Q5") (pin "2") (pinfunction "2_2") (pintype "passive"))
    )
    (net (code "89") (name "Net-(IC16-PR1)") (class "Default")
      (node (ref "C44") (pin "2") (pinfunction "2_2") (pintype "passive"))
      (node (ref "IC16") (pin "37") (pinfunction "PR1_37") (pintype "bidirectional"))
      (node (ref "Q5") (pin "1") (pinfunction "1_1") (pintype "passive"))
    )
    (net (code "90") (name "Net-(J1-2)") (class "Default")
      (node (ref "J1") (pin "P2") (pinfunction "2_P2") (pintype "passive"))
      (node (ref "R20") (pin "2") (pinfunction "2_2") (pintype "passive"))
    )
    (net (code "91") (name "Net-(J1-3)") (class "Default")
      (node (ref "J1") (pin "P3") (pinfunction "3_P3") (pintype "passive"))
      (node (ref "J5") (pin "P2") (pinfunction "2_P2") (pintype "passive"))
      (node (ref "R21") (pin "2") (pinfunction "2_2") (pintype "passive"))
    )
    (net (code "92") (name "Net-(J2-2)") (class "Default")
      (node (ref "C1") (pin "1") (pinfunction "1_1") (pintype "passive"))
      (node (ref "J2") (pin "P2") (pinfunction "2_P2") (pintype "passive"))
      (node (ref "R1") (pin "2") (pinfunction "2_2") (pintype "passive"))
      (node (ref "R2") (pin "1") (pinfunction "1_1") (pintype "passive"))
    )
    (net (code "93") (name "Net-(J4-2)") (class "Default")
      (node (ref "J4") (pin "P2") (pinfunction "2_P2") (pintype "passive"))
      (node (ref "R5") (pin "P$1") (pinfunction "E_P$1") (pintype "passive"))
    )
    (net (code "94") (name "Net-(J5-3)") (class "Default")
      (node (ref "J5") (pin "P3") (pinfunction "3_P3") (pintype "passive"))
      (node (ref "J9") (pin "P2") (pinfunction "2_P2") (pintype "passive"))
      (node (ref "R22") (pin "2") (pinfunction "2_2") (pintype "passive"))
    )
    (net (code "95") (name "Net-(J8-2)") (class "Default")
      (node (ref "J8") (pin "P2") (pinfunction "2_P2") (pintype "passive"))
      (node (ref "R32") (pin "P$1") (pinfunction "E_P$1") (pintype "passive"))
    )
    (net (code "96") (name "Net-(J12-2)") (class "Default")
      (node (ref "J12") (pin "P2") (pinfunction "2_P2") (pintype "passive"))
      (node (ref "R42") (pin "P$1") (pinfunction "E_P$1") (pintype "passive"))
    )
    (net (code "97") (name "Net-(J13-2)") (class "Default")
      (node (ref "J13") (pin "P2") (pinfunction "2_P2") (pintype "passive"))
      (node (ref "J9") (pin "P3") (pinfunction "3_P3") (pintype "passive"))
      (node (ref "R56") (pin "2") (pinfunction "2_2") (pintype "passive"))
    )
    (net (code "98") (name "Net-(J13-3)") (class "Default")
      (node (ref "J13") (pin "P3") (pinfunction "3_P3") (pintype "passive"))
      (node (ref "R57") (pin "2") (pinfunction "2_2") (pintype "passive"))
    )
    (net (code "99") (name "Net-(J16-2)") (class "Default")
      (node (ref "J16") (pin "P2") (pinfunction "2_P2") (pintype "passive"))
      (node (ref "R69") (pin "P$1") (pinfunction "E_P$1") (pintype "passive"))
    )
    (net (code "100") (name "Net-(J17-3)") (class "Default")
      (node (ref "J17") (pin "P3") (pinfunction "3_P3") (pintype "passive"))
      (node (ref "R33") (pin "2") (pinfunction "2_2") (pintype "passive"))
      (node (ref "R34") (pin "2") (pinfunction "2_2") (pintype "passive"))
    )
    (net (code "101") (name "Net-(LED1-PadA)") (class "Default")
      (node (ref "LED1") (pin "A") (pinfunction "A_A") (pintype "passive"))
      (node (ref "R71") (pin "2") (pinfunction "2_2") (pintype "passive"))
    )
    (net (code "102") (name "Net-(LED2-PadA)") (class "Default")
      (node (ref "LED2") (pin "A") (pinfunction "A_A") (pintype "passive"))
      (node (ref "R72") (pin "2") (pinfunction "2_2") (pintype "passive"))
    )
    (net (code "103") (name "Net-(LED3-PadA)") (class "Default")
      (node (ref "LED3") (pin "A") (pinfunction "A_A") (pintype "passive"))
      (node (ref "R73") (pin "2") (pinfunction "2_2") (pintype "passive"))
    )
    (net (code "104") (name "Net-(LED4-PadA)") (class "Default")
      (node (ref "LED4") (pin "A") (pinfunction "A_A") (pintype "passive"))
      (node (ref "R74") (pin "2") (pinfunction "2_2") (pintype "passive"))
    )
    (net (code "105") (name "Net-(Q1-PadB)") (class "Default")
      (node (ref "Q1") (pin "B") (pinfunction "B_B") (pintype "passive"))
      (node (ref "R21") (pin "1") (pinfunction "1_1") (pintype "passive"))
    )
    (net (code "106") (name "Net-(Q2-PadB)") (class "Default")
      (node (ref "Q2") (pin "B") (pinfunction "B_B") (pintype "passive"))
      (node (ref "R22") (pin "1") (pinfunction "1_1") (pintype "passive"))
    )
    (net (code "107") (name "Net-(Q3-PadB)") (class "Default")
      (node (ref "Q3") (pin "B") (pinfunction "B_B") (pintype "passive"))
      (node (ref "R56") (pin "1") (pinfunction "1_1") (pintype "passive"))
    )
    (net (code "108") (name "Net-(Q4-PadB)") (class "Default")
      (node (ref "Q4") (pin "B") (pinfunction "B_B") (pintype "passive"))
      (node (ref "R57") (pin "1") (pinfunction "1_1") (pintype "passive"))
    )
    (net (code "109") (name "PDICLK") (class "Default")
      (node (ref "IC16") (pin "35") (pinfunction "RESET_35") (pintype "bidirectional"))
      (node (ref "J20") (pin "5") (pinfunction "5_5") (pintype "passive"))
      (node (ref "R70") (pin "1") (pinfunction "1_1") (pintype "passive"))
    )
    (net (code "110") (name "PDIDATA") (class "Default")
      (node (ref "IC16") (pin "34") (pinfunction "PDI_DATA_34") (pintype "bidirectional"))
      (node (ref "J20") (pin "1") (pinfunction "1_1") (pintype "passive"))
    )
    (net (code "111") (name "SW1") (class "Default")
      (node (ref "IC16") (pin "4") (pinfunction "PB0_4") (pintype "bidirectional"))
      (node (ref "SW7") (pin "1") (pinfunction "1_1") (pintype "passive"))
      (node (ref "SW7") (pin "2") (pinfunction "2_2") (pintype "passive"))
    )
    (net (code "112") (name "SW2") (class "Default")
      (node (ref "IC16") (pin "5") (pinfunction "PB1_5") (pintype "bidirectional"))
      (node (ref "SW6") (pin "1") (pinfunction "1_1") (pintype "passive"))
      (node (ref "SW6") (pin "2") (pinfunction "2_2") (pintype "passive"))
    )
    (net (code "113") (name "SW3") (class "Default")
      (node (ref "IC16") (pin "6") (pinfunction "PB2_6") (pintype "bidirectional"))
      (node (ref "SW5") (pin "1") (pinfunction "1_1") (pintype "passive"))
      (node (ref "SW5") (pin "2") (pinfunction "2_2") (pintype "passive"))
    )
    (net (code "114") (name "SW4") (class "Default")
      (node (ref "IC16") (pin "7") (pinfunction "PB3_7") (pintype "bidirectional"))
      (node (ref "SW4") (pin "1") (pinfunction "1_1") (pintype "passive"))
      (node (ref "SW4") (pin "2") (pinfunction "2_2") (pintype "passive"))
    )
    (net (code "115") (name "SW_MIDI_LEARN") (class "Default")
      (node (ref "IC16") (pin "11") (pinfunction "PC1_11") (pintype "bidirectional"))
      (node (ref "J18") (pin "2") (pinfunction "2_2") (pintype "passive"))
    )
    (net (code "116") (name "SW_MIDI_MODE") (class "Default")
      (node (ref "IC16") (pin "13") (pinfunction "PC3_13") (pintype "bidirectional"))
      (node (ref "J18") (pin "6") (pinfunction "6_6") (pintype "passive"))
    )
    (net (code "117") (name "VCC") (class "Default")
      (node (ref "C15") (pin "1") (pinfunction "1_1") (pintype "passive"))
      (node (ref "C18") (pin "+") (pinfunction "+_+") (pintype "passive"))
      (node (ref "C22") (pin "1") (pinfunction "1_1") (pintype "passive"))
      (node (ref "C3") (pin "1") (pinfunction "1_1") (pintype "passive"))
      (node (ref "D1") (pin "A") (pinfunction "A_A") (pintype "passive"))
      (node (ref "D2") (pin "C") (pinfunction "C_C") (pintype "passive"))
      (node (ref "IC2") (pin "8") (pinfunction "V+_8") (pintype "power_in"))
      (node (ref "IC7") (pin "8") (pinfunction "V+_8") (pintype "power_in"))
      (node (ref "IC9") (pin "8") (pinfunction "V+_8") (pintype "power_in"))
      (node (ref "R2") (pin "2") (pinfunction "2_2") (pintype "passive"))
    )
    (net (code "118") (name "VEE") (class "Default")
      (node (ref "C11") (pin "2") (pinfunction "2_2") (pintype "passive"))
      (node (ref "C19") (pin "-") (pinfunction "-_-") (pintype "passive"))
      (node (ref "C20") (pin "2") (pinfunction "2_2") (pintype "passive"))
      (node (ref "C30") (pin "2") (pinfunction "2_2") (pintype "passive"))
      (node (ref "D3") (pin "A") (pinfunction "A_A") (pintype "passive"))
      (node (ref "IC2") (pin "4") (pinfunction "V-_4") (pintype "power_in"))
      (node (ref "IC7") (pin "4") (pinfunction "V-_4") (pintype "power_in"))
      (node (ref "IC9") (pin "4") (pinfunction "V-_4") (pintype "power_in"))
      (node (ref "R3") (pin "1") (pinfunction "1_1") (pintype "passive"))
    )
    (net (code "119") (name "unconnected-(IC15-OUTB-Pad6)") (class "Default")
      (node (ref "IC15") (pin "6") (pinfunction "OUTB_6") (pintype "output"))
    )
    (net (code "120") (name "unconnected-(IC16-PD1-Pad21)") (class "Default")
      (node (ref "IC16") (pin "21") (pinfunction "PD1_21") (pintype "bidirectional"))
    )
    (net (code "121") (name "unconnected-(IC16-PD2-Pad22)") (class "Default")
      (node (ref "IC16") (pin "22") (pinfunction "PD2_22") (pintype "bidirectional"))
    )
    (net (code "122") (name "unconnected-(IC16-PE1-Pad29)") (class "Default")
      (node (ref "IC16") (pin "29") (pinfunction "PE1_29") (pintype "bidirectional"))
    )
    (net (code "123") (name "unconnected-(IC16-PE2-Pad32)") (class "Default")
      (node (ref "IC16") (pin "32") (pinfunction "PE2_32") (pintype "bidirectional"))
    )
    (net (code "124") (name "unconnected-(IC16-PE3-Pad33)") (class "Default")
      (node (ref "IC16") (pin "33") (pinfunction "PE3_33") (pintype "bidirectional"))
    )
    (net (code "125") (name "unconnected-(J3-2-PadP2)") (class "Default")
      (node (ref "J3") (pin "P2") (pinfunction "2_P2") (pintype "passive"))
    )
    (net (code "126") (name "unconnected-(J7-2-PadP2)") (class "Default")
      (node (ref "J7") (pin "P2") (pinfunction "2_P2") (pintype "passive"))
    )
    (net (code "127") (name "unconnected-(J11-2-PadP2)") (class "Default")
      (node (ref "J11") (pin "P2") (pinfunction "2_P2") (pintype "passive"))
    )
    (net (code "128") (name "unconnected-(J15-2-PadP2)") (class "Default")
      (node (ref "J15") (pin "P2") (pinfunction "2_P2") (pintype "passive"))
    )
    (net (code "129") (name "unconnected-(J17-2-PadP2)") (class "Default")
      (node (ref "J17") (pin "P2") (pinfunction "2_P2") (pintype "passive"))
    )
    (net (code "130") (name "unconnected-(J20-Pad3)") (class "Default")
      (node (ref "J20") (pin "3") (pinfunction "3_3") (pintype "passive"))
    )
    (net (code "131") (name "unconnected-(J20-Pad4)") (class "Default")
      (node (ref "J20") (pin "4") (pinfunction "4_4") (pintype "passive"))
    )
  )
)
